# homeboard22.net
KiCad netlist of a schematic drawn in EAGLE
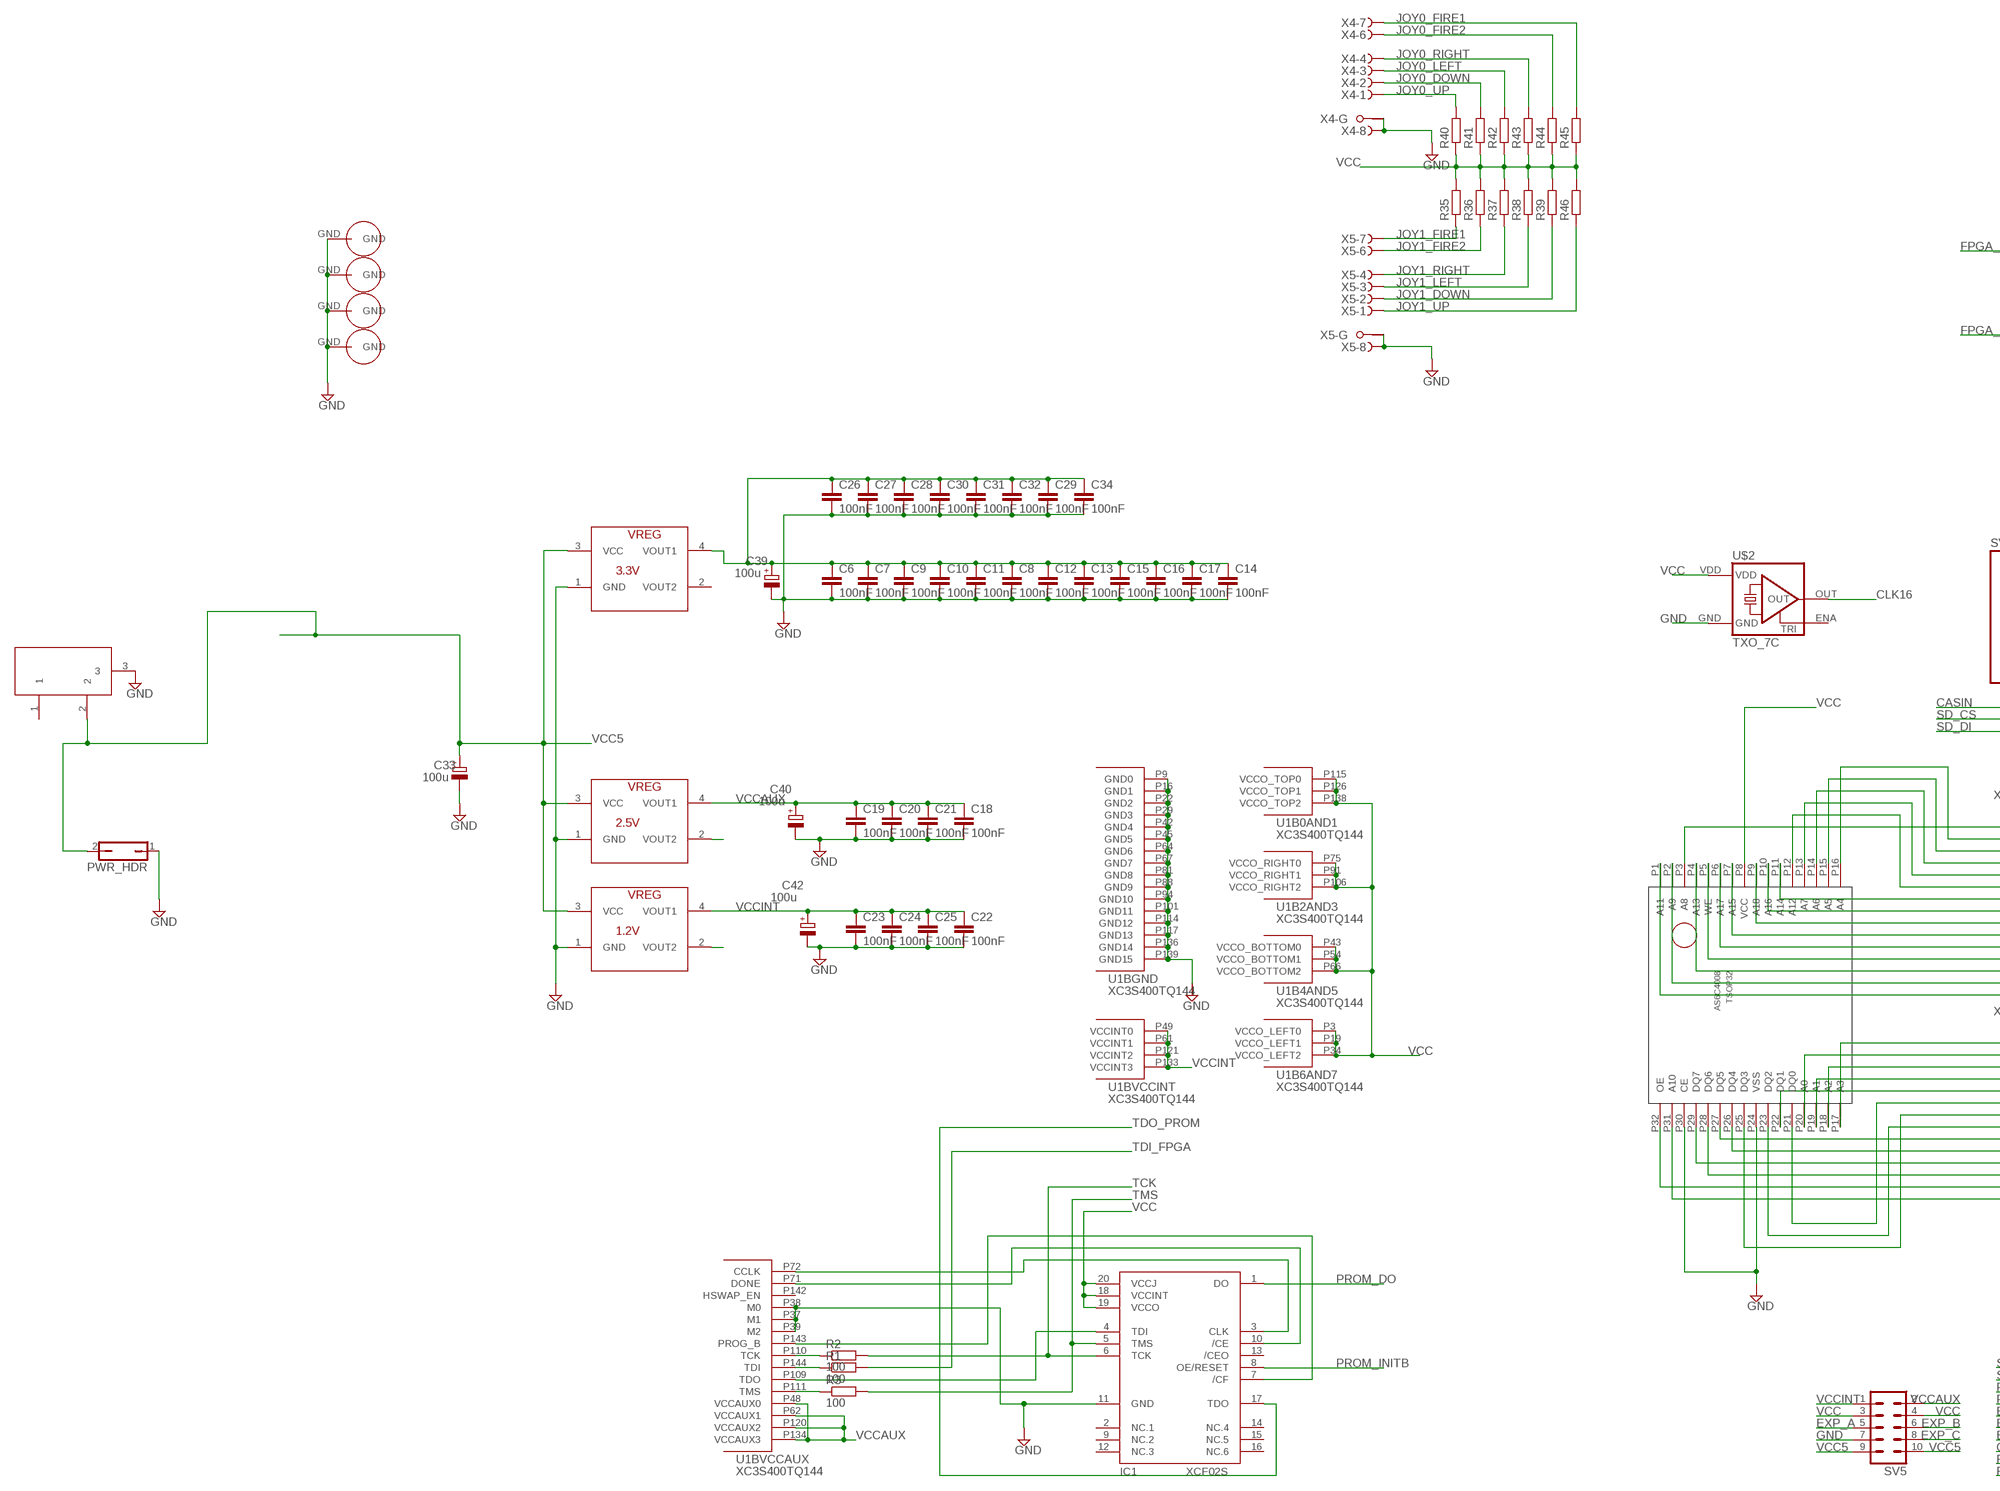
[diagram p0: schematic, sheet 1, part 1 of 3]
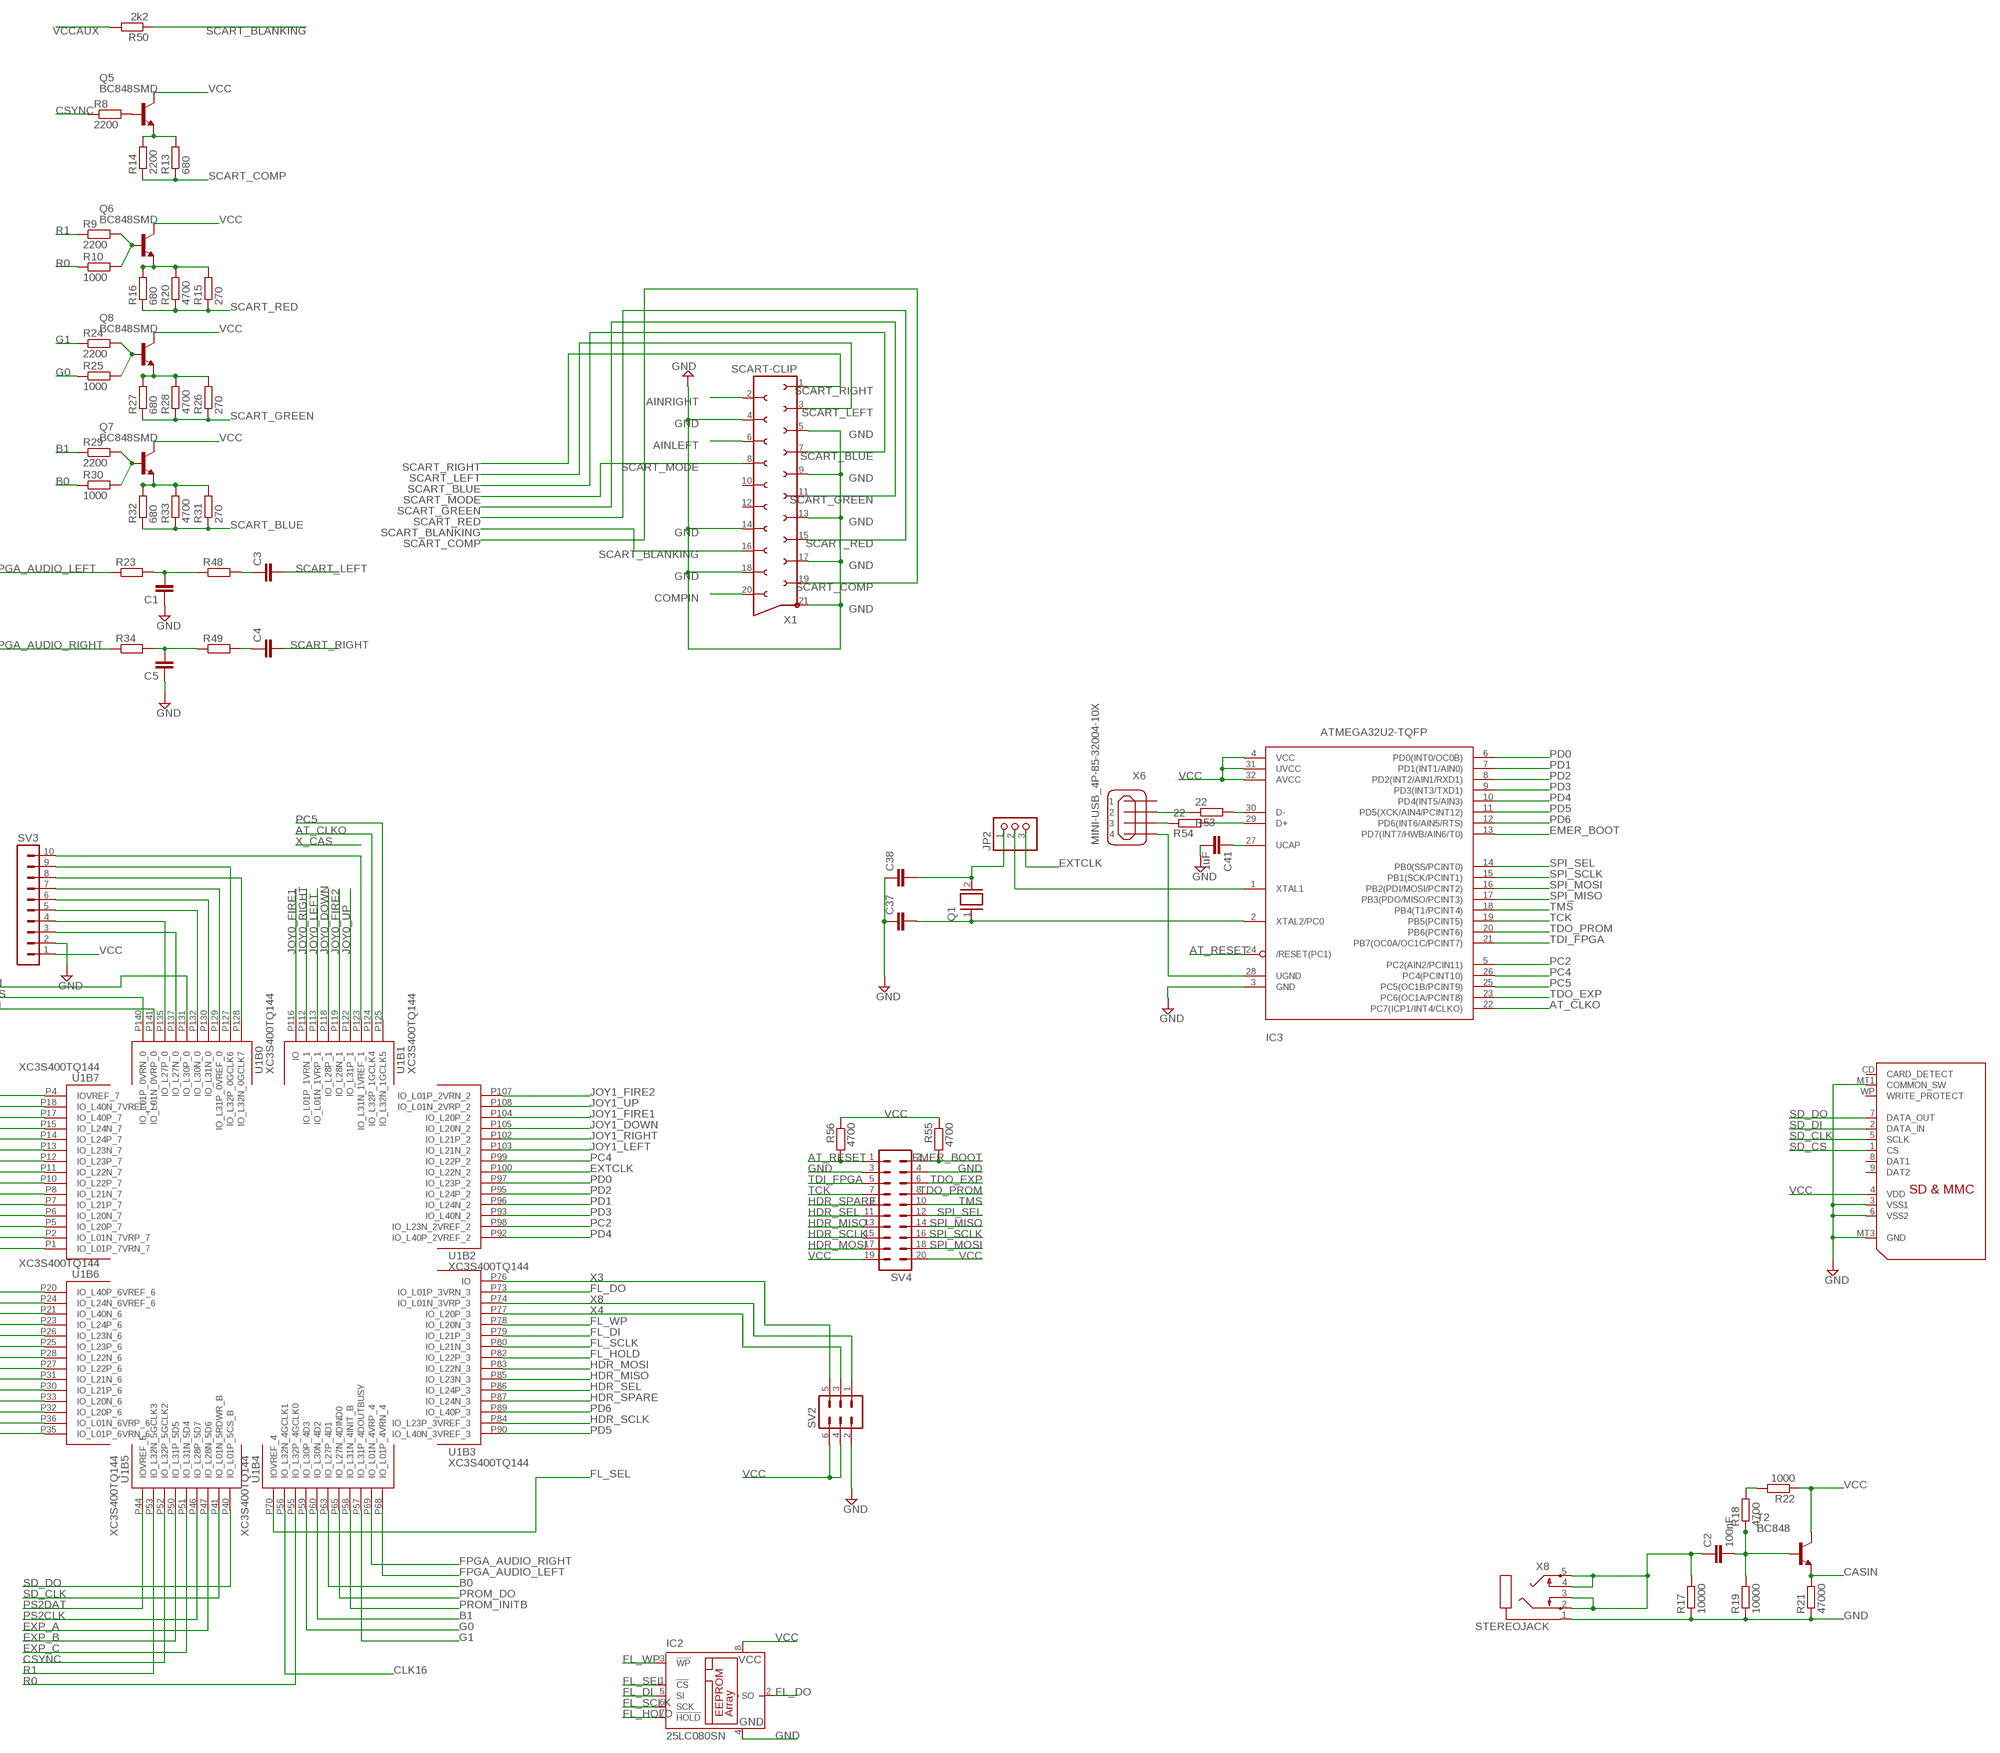
[diagram p1: schematic, sheet 1, part 2 of 3]
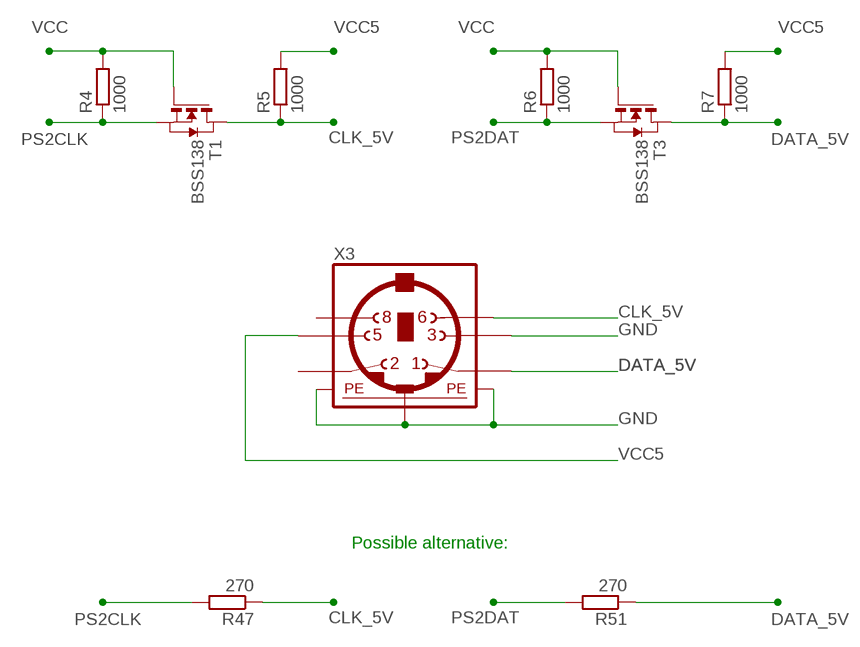
[diagram p2: schematic, sheet 1, part 3 of 3]

(export (version "E")
  (design (tool "Eeschema 10.0.6"))
  (components
    (comp (ref "C1")
      (value "C-EUC0603")
      (footprint "eagle-import:C0603")
      (libsource (lib "eagle-import") (part "resistor_C-EUC0603"))
    )
    (comp (ref "C2")
      (value "100nF")
      (footprint "eagle-import:C0603")
      (libsource (lib "eagle-import") (part "resistor_C-EUC0603"))
    )
    (comp (ref "C3")
      (value "C-EUC0603")
      (footprint "eagle-import:C0603")
      (libsource (lib "eagle-import") (part "resistor_C-EUC0603"))
    )
    (comp (ref "C4")
      (value "C-EUC0603")
      (footprint "eagle-import:C0603")
      (libsource (lib "eagle-import") (part "resistor_C-EUC0603"))
    )
    (comp (ref "C5")
      (value "C-EUC0603")
      (footprint "eagle-import:C0603")
      (libsource (lib "eagle-import") (part "resistor_C-EUC0603"))
    )
    (comp (ref "C6")
      (value "100nF")
      (footprint "eagle-import:C0603")
      (libsource (lib "eagle-import") (part "C-EUC0603"))
    )
    (comp (ref "C7")
      (value "100nF")
      (footprint "eagle-import:C0603")
      (libsource (lib "eagle-import") (part "C-EUC0603"))
    )
    (comp (ref "C8")
      (value "100nF")
      (footprint "eagle-import:C0603")
      (libsource (lib "eagle-import") (part "C-EUC0603"))
    )
    (comp (ref "C9")
      (value "100nF")
      (footprint "eagle-import:C0603")
      (libsource (lib "eagle-import") (part "C-EUC0603"))
    )
    (comp (ref "C10")
      (value "100nF")
      (footprint "eagle-import:C0603")
      (libsource (lib "eagle-import") (part "C-EUC0603"))
    )
    (comp (ref "C11")
      (value "100nF")
      (footprint "eagle-import:C0603")
      (libsource (lib "eagle-import") (part "C-EUC0603"))
    )
    (comp (ref "C12")
      (value "100nF")
      (footprint "eagle-import:C0603")
      (libsource (lib "eagle-import") (part "C-EUC0603"))
    )
    (comp (ref "C13")
      (value "100nF")
      (footprint "eagle-import:C0603")
      (libsource (lib "eagle-import") (part "C-EUC0603"))
    )
    (comp (ref "C14")
      (value "100nF")
      (footprint "eagle-import:C0603")
      (libsource (lib "eagle-import") (part "C-EUC0603"))
    )
    (comp (ref "C15")
      (value "100nF")
      (footprint "eagle-import:C0603")
      (libsource (lib "eagle-import") (part "C-EUC0603"))
    )
    (comp (ref "C16")
      (value "100nF")
      (footprint "eagle-import:C0603")
      (libsource (lib "eagle-import") (part "C-EUC0603"))
    )
    (comp (ref "C17")
      (value "100nF")
      (footprint "eagle-import:C0603")
      (libsource (lib "eagle-import") (part "C-EUC0603"))
    )
    (comp (ref "C18")
      (value "100nF")
      (footprint "eagle-import:C0603")
      (libsource (lib "eagle-import") (part "C-EUC0603"))
    )
    (comp (ref "C19")
      (value "100nF")
      (footprint "eagle-import:C0603")
      (libsource (lib "eagle-import") (part "C-EUC0603"))
    )
    (comp (ref "C20")
      (value "100nF")
      (footprint "eagle-import:C0603")
      (libsource (lib "eagle-import") (part "C-EUC0603"))
    )
    (comp (ref "C21")
      (value "100nF")
      (footprint "eagle-import:C0603")
      (libsource (lib "eagle-import") (part "C-EUC0603"))
    )
    (comp (ref "C22")
      (value "100nF")
      (footprint "eagle-import:C0603")
      (libsource (lib "eagle-import") (part "C-EUC0603"))
    )
    (comp (ref "C23")
      (value "100nF")
      (footprint "eagle-import:C0603")
      (libsource (lib "eagle-import") (part "C-EUC0603"))
    )
    (comp (ref "C24")
      (value "100nF")
      (footprint "eagle-import:C0603")
      (libsource (lib "eagle-import") (part "C-EUC0603"))
    )
    (comp (ref "C25")
      (value "100nF")
      (footprint "eagle-import:C0603")
      (libsource (lib "eagle-import") (part "C-EUC0603"))
    )
    (comp (ref "C26")
      (value "100nF")
      (footprint "eagle-import:C0603")
      (libsource (lib "eagle-import") (part "C-EUC0603"))
    )
    (comp (ref "C27")
      (value "100nF")
      (footprint "eagle-import:C0603")
      (libsource (lib "eagle-import") (part "C-EUC0603"))
    )
    (comp (ref "C28")
      (value "100nF")
      (footprint "eagle-import:C0603")
      (libsource (lib "eagle-import") (part "C-EUC0603"))
    )
    (comp (ref "C29")
      (value "100nF")
      (footprint "eagle-import:C0603")
      (libsource (lib "eagle-import") (part "C-EUC0603"))
    )
    (comp (ref "C30")
      (value "100nF")
      (footprint "eagle-import:C0603")
      (libsource (lib "eagle-import") (part "C-EUC0603"))
    )
    (comp (ref "C31")
      (value "100nF")
      (footprint "eagle-import:C0603")
      (libsource (lib "eagle-import") (part "C-EUC0603"))
    )
    (comp (ref "C32")
      (value "100nF")
      (footprint "eagle-import:C0603")
      (libsource (lib "eagle-import") (part "C-EUC0603"))
    )
    (comp (ref "C33")
      (value "100u")
      (footprint "eagle-import:PANASONIC_D")
      (libsource (lib "eagle-import") (part "CPOL-EUD"))
    )
    (comp (ref "C34")
      (value "100nF")
      (footprint "eagle-import:C0603")
      (libsource (lib "eagle-import") (part "C-EUC0603"))
    )
    (comp (ref "C37")
      (value "C-EUC0805")
      (footprint "eagle-import:C0805")
      (libsource (lib "eagle-import") (part "C-EUC0805"))
    )
    (comp (ref "C38")
      (value "C-EUC0805")
      (footprint "eagle-import:C0805")
      (libsource (lib "eagle-import") (part "C-EUC0805"))
    )
    (comp (ref "C39")
      (value "100u")
      (footprint "eagle-import:PANASONIC_D")
      (libsource (lib "eagle-import") (part "CPOL-EUD"))
    )
    (comp (ref "C40")
      (value "100u")
      (footprint "eagle-import:PANASONIC_D")
      (libsource (lib "eagle-import") (part "CPOL-EUD"))
    )
    (comp (ref "C41")
      (value "1uF")
      (footprint "eagle-import:C0805")
      (libsource (lib "eagle-import") (part "C-EUC0805"))
    )
    (comp (ref "C42")
      (value "100u")
      (footprint "eagle-import:PANASONIC_D")
      (libsource (lib "eagle-import") (part "CPOL-EUD"))
    )
    (comp (ref "IC1")
      (value "XCF02S")
      (footprint "eagle-import:VO20")
      (libsource (lib "eagle-import") (part "XCF02S"))
    )
    (comp (ref "IC2")
      (value "25LC080SN")
      (footprint "eagle-import:SO-08")
      (fields (field (name "MF") "MICROCHIP") (field (name "MPN") "25LC080/SN"))
      (libsource (lib "eagle-import") (part "25SNLC080"))
    )
    (comp (ref "IC3")
      (value "ATMEGA32U2-TQFP")
      (footprint "eagle-import:TQFP32-08")
      (libsource (lib "eagle-import") (part "ATMEGA32U2-TQFP"))
    )
    (comp (ref "JP2")
      (value "PINHD-1X3")
      (footprint "eagle-import:1X03")
      (libsource (lib "eagle-import") (part "PINHD-1X3"))
    )
    (comp (ref "PWR_HDR")
      (value "JP1Q")
      (footprint "eagle-import:JP1")
      (libsource (lib "eagle-import") (part "JP1Q"))
    )
    (comp (ref "Q1")
      (value "XTAL/S")
      (footprint "eagle-import:QS")
      (libsource (lib "eagle-import") (part "XTAL/S"))
    )
    (comp (ref "Q5")
      (value "BC848SMD")
      (footprint "eagle-import:SOT23")
      (libsource (lib "eagle-import") (part "BC848SMD"))
    )
    (comp (ref "Q6")
      (value "BC848SMD")
      (footprint "eagle-import:SOT23")
      (libsource (lib "eagle-import") (part "BC848SMD"))
    )
    (comp (ref "Q7")
      (value "BC848SMD")
      (footprint "eagle-import:SOT23")
      (libsource (lib "eagle-import") (part "BC848SMD"))
    )
    (comp (ref "Q8")
      (value "BC848SMD")
      (footprint "eagle-import:SOT23")
      (libsource (lib "eagle-import") (part "BC848SMD"))
    )
    (comp (ref "R1")
      (value "100")
      (footprint "eagle-import:R0805")
      (libsource (lib "eagle-import") (part "R-EU_R0805"))
    )
    (comp (ref "R2")
      (value "100")
      (footprint "eagle-import:R0805")
      (libsource (lib "eagle-import") (part "R-EU_R0805"))
    )
    (comp (ref "R3")
      (value "100")
      (footprint "eagle-import:R0805")
      (libsource (lib "eagle-import") (part "R-EU_R0805"))
    )
    (comp (ref "R4")
      (value "1000")
      (footprint "eagle-import:R0805")
      (libsource (lib "eagle-import") (part "R-EU_R0805"))
    )
    (comp (ref "R5")
      (value "1000")
      (footprint "eagle-import:R0805")
      (libsource (lib "eagle-import") (part "R-EU_R0805"))
    )
    (comp (ref "R6")
      (value "1000")
      (footprint "eagle-import:R0805")
      (libsource (lib "eagle-import") (part "R-EU_R0805"))
    )
    (comp (ref "R7")
      (value "1000")
      (footprint "eagle-import:R0805")
      (libsource (lib "eagle-import") (part "R-EU_R0805"))
    )
    (comp (ref "R8")
      (value "2200")
      (footprint "eagle-import:R0805")
      (libsource (lib "eagle-import") (part "R-EU_R0805"))
    )
    (comp (ref "R9")
      (value "2200")
      (footprint "eagle-import:R0805")
      (libsource (lib "eagle-import") (part "R-EU_R0805"))
    )
    (comp (ref "R10")
      (value "1000")
      (footprint "eagle-import:R0805")
      (libsource (lib "eagle-import") (part "R-EU_R0805"))
    )
    (comp (ref "R13")
      (value "680")
      (footprint "eagle-import:R0805")
      (libsource (lib "eagle-import") (part "R-EU_R0805"))
    )
    (comp (ref "R14")
      (value "2200")
      (footprint "eagle-import:R0805")
      (libsource (lib "eagle-import") (part "R-EU_R0805"))
    )
    (comp (ref "R15")
      (value "270")
      (footprint "eagle-import:R0805")
      (libsource (lib "eagle-import") (part "R-EU_R0805"))
    )
    (comp (ref "R16")
      (value "680")
      (footprint "eagle-import:R0805")
      (libsource (lib "eagle-import") (part "R-EU_R0805"))
    )
    (comp (ref "R17")
      (value "10000")
      (footprint "eagle-import:R0805")
      (libsource (lib "eagle-import") (part "R-EU_R0805"))
    )
    (comp (ref "R18")
      (value "4700")
      (footprint "eagle-import:R0805")
      (libsource (lib "eagle-import") (part "R-EU_R0805"))
    )
    (comp (ref "R19")
      (value "10000")
      (footprint "eagle-import:R0805")
      (libsource (lib "eagle-import") (part "R-EU_R0805"))
    )
    (comp (ref "R20")
      (value "4700")
      (footprint "eagle-import:R0805")
      (libsource (lib "eagle-import") (part "R-EU_R0805"))
    )
    (comp (ref "R21")
      (value "47000")
      (footprint "eagle-import:R0805")
      (libsource (lib "eagle-import") (part "R-EU_R0805"))
    )
    (comp (ref "R22")
      (value "1000")
      (footprint "eagle-import:R0805")
      (libsource (lib "eagle-import") (part "R-EU_R0805"))
    )
    (comp (ref "R23")
      (value "R-EU_M0805")
      (footprint "eagle-import:M0805")
      (libsource (lib "eagle-import") (part "resistor_R-EU_M0805"))
    )
    (comp (ref "R24")
      (value "2200")
      (footprint "eagle-import:R0805")
      (libsource (lib "eagle-import") (part "R-EU_R0805"))
    )
    (comp (ref "R25")
      (value "1000")
      (footprint "eagle-import:R0805")
      (libsource (lib "eagle-import") (part "R-EU_R0805"))
    )
    (comp (ref "R26")
      (value "270")
      (footprint "eagle-import:R0805")
      (libsource (lib "eagle-import") (part "R-EU_R0805"))
    )
    (comp (ref "R27")
      (value "680")
      (footprint "eagle-import:R0805")
      (libsource (lib "eagle-import") (part "R-EU_R0805"))
    )
    (comp (ref "R28")
      (value "4700")
      (footprint "eagle-import:R0805")
      (libsource (lib "eagle-import") (part "R-EU_R0805"))
    )
    (comp (ref "R29")
      (value "2200")
      (footprint "eagle-import:R0805")
      (libsource (lib "eagle-import") (part "R-EU_R0805"))
    )
    (comp (ref "R30")
      (value "1000")
      (footprint "eagle-import:R0805")
      (libsource (lib "eagle-import") (part "R-EU_R0805"))
    )
    (comp (ref "R31")
      (value "270")
      (footprint "eagle-import:R0805")
      (libsource (lib "eagle-import") (part "R-EU_R0805"))
    )
    (comp (ref "R32")
      (value "680")
      (footprint "eagle-import:R0805")
      (libsource (lib "eagle-import") (part "R-EU_R0805"))
    )
    (comp (ref "R33")
      (value "4700")
      (footprint "eagle-import:R0805")
      (libsource (lib "eagle-import") (part "R-EU_R0805"))
    )
    (comp (ref "R34")
      (value "R-EU_M0805")
      (footprint "eagle-import:M0805")
      (libsource (lib "eagle-import") (part "resistor_R-EU_M0805"))
    )
    (comp (ref "R35")
      (value "R-EU_M0805")
      (footprint "eagle-import:M0805")
      (libsource (lib "eagle-import") (part "resistor_R-EU_M0805"))
    )
    (comp (ref "R36")
      (value "R-EU_M0805")
      (footprint "eagle-import:M0805")
      (libsource (lib "eagle-import") (part "resistor_R-EU_M0805"))
    )
    (comp (ref "R37")
      (value "R-EU_M0805")
      (footprint "eagle-import:M0805")
      (libsource (lib "eagle-import") (part "resistor_R-EU_M0805"))
    )
    (comp (ref "R38")
      (value "R-EU_M0805")
      (footprint "eagle-import:M0805")
      (libsource (lib "eagle-import") (part "resistor_R-EU_M0805"))
    )
    (comp (ref "R39")
      (value "R-EU_M0805")
      (footprint "eagle-import:M0805")
      (libsource (lib "eagle-import") (part "resistor_R-EU_M0805"))
    )
    (comp (ref "R40")
      (value "R-EU_M0805")
      (footprint "eagle-import:M0805")
      (libsource (lib "eagle-import") (part "resistor_R-EU_M0805"))
    )
    (comp (ref "R41")
      (value "R-EU_M0805")
      (footprint "eagle-import:M0805")
      (libsource (lib "eagle-import") (part "resistor_R-EU_M0805"))
    )
    (comp (ref "R42")
      (value "R-EU_M0805")
      (footprint "eagle-import:M0805")
      (libsource (lib "eagle-import") (part "resistor_R-EU_M0805"))
    )
    (comp (ref "R43")
      (value "R-EU_M0805")
      (footprint "eagle-import:M0805")
      (libsource (lib "eagle-import") (part "resistor_R-EU_M0805"))
    )
    (comp (ref "R44")
      (value "R-EU_M0805")
      (footprint "eagle-import:M0805")
      (libsource (lib "eagle-import") (part "resistor_R-EU_M0805"))
    )
    (comp (ref "R45")
      (value "R-EU_M0805")
      (footprint "eagle-import:M0805")
      (libsource (lib "eagle-import") (part "resistor_R-EU_M0805"))
    )
    (comp (ref "R46")
      (value "R-EU_M0805")
      (footprint "eagle-import:M0805")
      (libsource (lib "eagle-import") (part "resistor_R-EU_M0805"))
    )
    (comp (ref "R47")
      (value "270")
      (footprint "eagle-import:R0805")
      (libsource (lib "eagle-import") (part "R-EU_R0805"))
    )
    (comp (ref "R48")
      (value "R-EU_M0805")
      (footprint "eagle-import:M0805")
      (libsource (lib "eagle-import") (part "resistor_R-EU_M0805"))
    )
    (comp (ref "R49")
      (value "R-EU_M0805")
      (footprint "eagle-import:M0805")
      (libsource (lib "eagle-import") (part "resistor_R-EU_M0805"))
    )
    (comp (ref "R50")
      (value "2k2")
      (footprint "eagle-import:M0805")
      (libsource (lib "eagle-import") (part "resistor_R-EU_M0805"))
    )
    (comp (ref "R51")
      (value "270")
      (footprint "eagle-import:R0805")
      (libsource (lib "eagle-import") (part "R-EU_R0805"))
    )
    (comp (ref "R53")
      (value "22")
      (footprint "eagle-import:R0805")
      (libsource (lib "eagle-import") (part "R-EU_R0805"))
    )
    (comp (ref "R54")
      (value "22")
      (footprint "eagle-import:R0805")
      (libsource (lib "eagle-import") (part "R-EU_R0805"))
    )
    (comp (ref "R55")
      (value "4700")
      (footprint "eagle-import:R0805")
      (libsource (lib "eagle-import") (part "R-EU_R0805"))
    )
    (comp (ref "R56")
      (value "4700")
      (footprint "eagle-import:R0805")
      (libsource (lib "eagle-import") (part "R-EU_R0805"))
    )
    (comp (ref "REG1.2")
      (value "1.2V")
      (footprint "eagle-import:SOT223")
      (libsource (lib "eagle-import") (part "NX1117"))
    )
    (comp (ref "REG2.5")
      (value "2.5V")
      (footprint "eagle-import:SOT223")
      (libsource (lib "eagle-import") (part "NX1117"))
    )
    (comp (ref "SV2")
      (value "MA03-2")
      (footprint "eagle-import:MA03-2")
      (libsource (lib "eagle-import") (part "MA03-2"))
    )
    (comp (ref "SV3")
      (value "MA10-1")
      (footprint "eagle-import:MA10-1")
      (libsource (lib "eagle-import") (part "MA10-1"))
    )
    (comp (ref "SV4")
      (value "MA10-2")
      (footprint "eagle-import:MA10-2")
      (libsource (lib "eagle-import") (part "MA10-2"))
    )
    (comp (ref "SV5")
      (value "MA05-2")
      (footprint "eagle-import:MA05-2")
      (libsource (lib "eagle-import") (part "MA05-2"))
    )
    (comp (ref "T1")
      (value "BSS138")
      (footprint "eagle-import:SOT-23")
      (libsource (lib "eagle-import") (part "NMOSSOT23"))
    )
    (comp (ref "T2")
      (value "BC848")
      (footprint "eagle-import:SOT23")
      (libsource (lib "eagle-import") (part "BC848"))
    )
    (comp (ref "T3")
      (value "BSS138")
      (footprint "eagle-import:SOT-23")
      (libsource (lib "eagle-import") (part "NMOSSOT23"))
    )
    (comp (ref "U$1")
      (value "GNDHOLE")
      (footprint "eagle-import:GNDHOLE")
      (libsource (lib "eagle-import") (part "GNDHOLE"))
    )
    (comp (ref "U$2")
      (value "TXO_7C")
      (footprint "eagle-import:OSC_7C")
      (libsource (lib "eagle-import") (part "TXO_7C"))
    )
    (comp (ref "U$3")
      (value "SDMMCNOHOLE")
      (footprint "eagle-import:SDCARD-NOHOLE")
      (libsource (lib "eagle-import") (part "SDMMCNOHOLE"))
    )
    (comp (ref "U$4")
      (value "3.3V")
      (footprint "eagle-import:SOT223")
      (libsource (lib "eagle-import") (part "NX1117"))
    )
    (comp (ref "U$6")
      (value "AS6C4008")
      (footprint "eagle-import:TSOP32")
      (libsource (lib "eagle-import") (part "AS6C4008"))
    )
    (comp (ref "U$7")
      (value "GNDHOLE")
      (footprint "eagle-import:GNDHOLE")
      (libsource (lib "eagle-import") (part "GNDHOLE"))
    )
    (comp (ref "U$8")
      (value "GNDHOLE")
      (footprint "eagle-import:GNDHOLE")
      (libsource (lib "eagle-import") (part "GNDHOLE"))
    )
    (comp (ref "U$9")
      (value "GNDHOLE")
      (footprint "eagle-import:GNDHOLE")
      (libsource (lib "eagle-import") (part "GNDHOLE"))
    )
    (comp (ref "U1")
      (value "XC3S400TQ144")
      (footprint "eagle-import:TQ144")
      (libsource (lib "eagle-import") (part "XC3S400TQ144"))
    )
    (comp (ref "X1")
      (value "SCART-CLIP")
      (footprint "eagle-import:SCART-CLIP")
      (libsource (lib "eagle-import") (part "SCART-CLIP"))
    )
    (comp (ref "X3")
      (value "MINI_DIN_6")
      (footprint "eagle-import:M_DIN6")
      (libsource (lib "eagle-import") (part "MINI_DIN_6"))
    )
    (comp (ref "X4")
      (value "F09HPS")
      (footprint "eagle-import:F09HP")
      (libsource (lib "eagle-import") (part "F09HPS"))
    )
    (comp (ref "X5")
      (value "F09HPS")
      (footprint "eagle-import:F09HP")
      (libsource (lib "eagle-import") (part "F09HPS"))
    )
    (comp (ref "X6")
      (value "MINI-USB_4P-85-32004-10X")
      (footprint "eagle-import:85-32004-10X")
      (libsource (lib "eagle-import") (part "MINI-USB_4P-85-32004-10X"))
    )
    (comp (ref "X7")
      (value "DC21MMX")
      (footprint "eagle-import:DC-21MM")
      (libsource (lib "eagle-import") (part "DC21MMX"))
    )
    (comp (ref "X8")
      (value "STEREOJACK")
      (footprint "eagle-import:20-0137")
      (libsource (lib "eagle-import") (part "STEREOJACK"))
    )
  )
  (nets
    (net (code "1") (name "/1") (class "Default")
      (node (ref "X7") (pin "1") (pinfunction "1_1") (pintype "power_in"))
    )
    (net (code "2") (name "/AINLEFT") (class "Default")
      (node (ref "X1") (pin "6") (pinfunction "6_6") (pintype "passive"))
    )
    (net (code "3") (name "/AINRIGHT") (class "Default")
      (node (ref "X1") (pin "2") (pinfunction "2_2") (pintype "passive"))
    )
    (net (code "4") (name "/AT_CLKO") (class "Default")
      (node (ref "IC3") (pin "22") (pinfunction "PC7(ICP1/INT4/CLKO)_22") (pintype "bidirectional"))
      (node (ref "U1") (pin "P124") (pinfunction "IO_L32P_1GCLK4_P124") (pintype "bidirectional"))
    )
    (net (code "5") (name "/AT_RESET") (class "Default")
      (node (ref "IC3") (pin "24") (pinfunction "/RESET(PC1)_24") (pintype "bidirectional"))
      (node (ref "R56") (pin "2") (pinfunction "2_2") (pintype "passive"))
      (node (ref "SV4") (pin "1") (pinfunction "1_1") (pintype "passive"))
    )
    (net (code "6") (name "/B0") (class "Default")
      (node (ref "R30") (pin "1") (pinfunction "1_1") (pintype "passive"))
      (node (ref "U1") (pin "P63") (pinfunction "IO_L27P_4D1_P63") (pintype "bidirectional"))
    )
    (net (code "7") (name "/B1") (class "Default")
      (node (ref "R29") (pin "1") (pinfunction "1_1") (pintype "passive"))
      (node (ref "U1") (pin "P60") (pinfunction "IO_L30N_4D2_P60") (pintype "bidirectional"))
    )
    (net (code "8") (name "/CASIN") (class "Default")
      (node (ref "R21") (pin "2") (pinfunction "2_2") (pintype "passive"))
      (node (ref "T2") (pin "2") (pinfunction "E_2") (pintype "passive"))
      (node (ref "U1") (pin "P131") (pinfunction "IO_L30P_0_P131") (pintype "bidirectional"))
    )
    (net (code "9") (name "/CLK16") (class "Default")
      (node (ref "U$2") (pin "OUT") (pinfunction "OUT_OUT") (pintype "output"))
      (node (ref "U1") (pin "P56") (pinfunction "IO_L32N_4GCLK1_P56") (pintype "bidirectional"))
    )
    (net (code "10") (name "/CLK_5V") (class "Default")
      (node (ref "R47") (pin "1") (pinfunction "1_1") (pintype "passive"))
      (node (ref "R5") (pin "1") (pinfunction "1_1") (pintype "passive"))
      (node (ref "T1") (pin "1") (pinfunction "D_1") (pintype "passive"))
      (node (ref "X3") (pin "6") (pinfunction "6_6") (pintype "passive"))
    )
    (net (code "11") (name "/COMPIN") (class "Default")
      (node (ref "X1") (pin "20") (pinfunction "20_20") (pintype "passive"))
    )
    (net (code "12") (name "/CSYNC") (class "Default")
      (node (ref "R8") (pin "1") (pinfunction "1_1") (pintype "passive"))
      (node (ref "U1") (pin "P52") (pinfunction "IO_L32P_5GCLK2_P52") (pintype "bidirectional"))
    )
    (net (code "13") (name "/DATA_5V") (class "Default")
      (node (ref "R51") (pin "1") (pinfunction "1_1") (pintype "passive"))
      (node (ref "R7") (pin "1") (pinfunction "1_1") (pintype "passive"))
      (node (ref "T3") (pin "1") (pinfunction "D_1") (pintype "passive"))
      (node (ref "X3") (pin "1") (pinfunction "1_1") (pintype "passive"))
    )
    (net (code "14") (name "/EMER_BOOT") (class "Default")
      (node (ref "IC3") (pin "13") (pinfunction "PD7(INT7/HWB/AIN6/T0)_13") (pintype "bidirectional"))
      (node (ref "R55") (pin "2") (pinfunction "2_2") (pintype "passive"))
      (node (ref "SV4") (pin "2") (pinfunction "2_2") (pintype "passive"))
    )
    (net (code "15") (name "/EXP_A") (class "Default")
      (node (ref "SV5") (pin "5") (pinfunction "5_5") (pintype "passive"))
      (node (ref "U1") (pin "P47") (pinfunction "IO_L28N_5D6_P47") (pintype "bidirectional"))
    )
    (net (code "16") (name "/EXP_B") (class "Default")
      (node (ref "SV5") (pin "6") (pinfunction "6_6") (pintype "passive"))
      (node (ref "U1") (pin "P50") (pinfunction "IO_L31P_5D5_P50") (pintype "bidirectional"))
    )
    (net (code "17") (name "/EXP_C") (class "Default")
      (node (ref "SV5") (pin "8") (pinfunction "8_8") (pintype "passive"))
      (node (ref "U1") (pin "P51") (pinfunction "IO_L31N_5D4_P51") (pintype "bidirectional"))
    )
    (net (code "18") (name "/EXTCLK") (class "Default")
      (node (ref "JP2") (pin "3") (pinfunction "3_3") (pintype "passive"))
      (node (ref "U1") (pin "P100") (pinfunction "IO_L22N_2_P100") (pintype "bidirectional"))
    )
    (net (code "19") (name "/FL_DI") (class "Default")
      (node (ref "IC2") (pin "5") (pinfunction "SI_5") (pintype "input"))
      (node (ref "U1") (pin "P79") (pinfunction "IO_L21P_3_P79") (pintype "bidirectional"))
    )
    (net (code "20") (name "/FL_DO") (class "Default")
      (node (ref "IC2") (pin "2") (pinfunction "SO_2") (pintype "bidirectional"))
      (node (ref "U1") (pin "P73") (pinfunction "IO_L01P_3VRN_3_P73") (pintype "bidirectional"))
    )
    (net (code "21") (name "/FL_HOLD") (class "Default")
      (node (ref "IC2") (pin "7") (pinfunction "~{HOLD}_7") (pintype "input"))
      (node (ref "U1") (pin "P82") (pinfunction "IO_L22P_3_P82") (pintype "bidirectional"))
    )
    (net (code "22") (name "/FL_SCLK") (class "Default")
      (node (ref "IC2") (pin "6") (pinfunction "SCK_6") (pintype "input"))
      (node (ref "U1") (pin "P80") (pinfunction "IO_L21N_3_P80") (pintype "bidirectional"))
    )
    (net (code "23") (name "/FL_SEL") (class "Default")
      (node (ref "IC2") (pin "1") (pinfunction "~{CS}_1") (pintype "input"))
      (node (ref "U1") (pin "P70") (pinfunction "IOVREF_4_P70") (pintype "bidirectional"))
    )
    (net (code "24") (name "/FL_WP") (class "Default")
      (node (ref "IC2") (pin "3") (pinfunction "~{WP}_3") (pintype "input"))
      (node (ref "U1") (pin "P78") (pinfunction "IO_L20N_3_P78") (pintype "bidirectional"))
    )
    (net (code "25") (name "/FPGA_AUDIO_LEFT") (class "Default")
      (node (ref "R23") (pin "1") (pinfunction "1_1") (pintype "passive"))
      (node (ref "U1") (pin "P68") (pinfunction "IO_L01P_4VRN_4_P68") (pintype "bidirectional"))
    )
    (net (code "26") (name "/FPGA_AUDIO_RIGHT") (class "Default")
      (node (ref "R34") (pin "1") (pinfunction "1_1") (pintype "passive"))
      (node (ref "U1") (pin "P69") (pinfunction "IO_L01N_4VRP_4_P69") (pintype "bidirectional"))
    )
    (net (code "27") (name "/G0") (class "Default")
      (node (ref "R25") (pin "1") (pinfunction "1_1") (pintype "passive"))
      (node (ref "U1") (pin "P59") (pinfunction "IO_L30P_4D3_P59") (pintype "bidirectional"))
    )
    (net (code "28") (name "/G1") (class "Default")
      (node (ref "R24") (pin "1") (pinfunction "1_1") (pintype "passive"))
      (node (ref "U1") (pin "P57") (pinfunction "IO_L31P_4DOUTBUSY_P57") (pintype "bidirectional"))
    )
    (net (code "29") (name "/HDR_MISO") (class "Default")
      (node (ref "SV4") (pin "13") (pinfunction "13_13") (pintype "passive"))
      (node (ref "U1") (pin "P85") (pinfunction "IO_L23N_3_P85") (pintype "bidirectional"))
    )
    (net (code "30") (name "/HDR_MOSI") (class "Default")
      (node (ref "SV4") (pin "17") (pinfunction "17_17") (pintype "passive"))
      (node (ref "U1") (pin "P83") (pinfunction "IO_L22N_3_P83") (pintype "bidirectional"))
    )
    (net (code "31") (name "/HDR_SCLK") (class "Default")
      (node (ref "SV4") (pin "15") (pinfunction "15_15") (pintype "passive"))
      (node (ref "U1") (pin "P84") (pinfunction "IO_L23P_3VREF_3_P84") (pintype "bidirectional"))
    )
    (net (code "32") (name "/HDR_SEL") (class "Default")
      (node (ref "SV4") (pin "11") (pinfunction "11_11") (pintype "passive"))
      (node (ref "U1") (pin "P86") (pinfunction "IO_L24P_3_P86") (pintype "bidirectional"))
    )
    (net (code "33") (name "/HDR_SPARE") (class "Default")
      (node (ref "SV4") (pin "9") (pinfunction "9_9") (pintype "passive"))
      (node (ref "U1") (pin "P87") (pinfunction "IO_L24N_3_P87") (pintype "bidirectional"))
    )
    (net (code "34") (name "/JOY0_DOWN") (class "Default")
      (node (ref "R41") (pin "2") (pinfunction "2_2") (pintype "passive"))
      (node (ref "U1") (pin "P118") (pinfunction "IO_L28P_1_P118") (pintype "bidirectional"))
      (node (ref "X4") (pin "2") (pinfunction "F_2") (pintype "passive"))
    )
    (net (code "35") (name "/JOY0_FIRE1") (class "Default")
      (node (ref "R45") (pin "2") (pinfunction "2_2") (pintype "passive"))
      (node (ref "U1") (pin "P116") (pinfunction "IO_P116") (pintype "bidirectional"))
      (node (ref "X4") (pin "7") (pinfunction "F_7") (pintype "passive"))
    )
    (net (code "36") (name "/JOY0_FIRE2") (class "Default")
      (node (ref "R44") (pin "2") (pinfunction "2_2") (pintype "passive"))
      (node (ref "U1") (pin "P119") (pinfunction "IO_L28N_1_P119") (pintype "bidirectional"))
      (node (ref "X4") (pin "6") (pinfunction "F_6") (pintype "passive"))
    )
    (net (code "37") (name "/JOY0_LEFT") (class "Default")
      (node (ref "R42") (pin "2") (pinfunction "2_2") (pintype "passive"))
      (node (ref "U1") (pin "P113") (pinfunction "IO_L01N_1VRP_1_P113") (pintype "bidirectional"))
      (node (ref "X4") (pin "3") (pinfunction "F_3") (pintype "passive"))
    )
    (net (code "38") (name "/JOY0_RIGHT") (class "Default")
      (node (ref "R43") (pin "2") (pinfunction "2_2") (pintype "passive"))
      (node (ref "U1") (pin "P112") (pinfunction "IO_L01P_1VRN_1_P112") (pintype "bidirectional"))
      (node (ref "X4") (pin "4") (pinfunction "F_4") (pintype "passive"))
    )
    (net (code "39") (name "/JOY0_UP") (class "Default")
      (node (ref "R40") (pin "2") (pinfunction "2_2") (pintype "passive"))
      (node (ref "U1") (pin "P122") (pinfunction "IO_L31P_1_P122") (pintype "bidirectional"))
      (node (ref "X4") (pin "1") (pinfunction "F_1") (pintype "passive"))
    )
    (net (code "40") (name "/JOY1_DOWN") (class "Default")
      (node (ref "R39") (pin "1") (pinfunction "1_1") (pintype "passive"))
      (node (ref "U1") (pin "P105") (pinfunction "IO_L20N_2_P105") (pintype "bidirectional"))
      (node (ref "X5") (pin "2") (pinfunction "F_2") (pintype "passive"))
    )
    (net (code "41") (name "/JOY1_FIRE1") (class "Default")
      (node (ref "R35") (pin "1") (pinfunction "1_1") (pintype "passive"))
      (node (ref "U1") (pin "P104") (pinfunction "IO_L20P_2_P104") (pintype "bidirectional"))
      (node (ref "X5") (pin "7") (pinfunction "F_7") (pintype "passive"))
    )
    (net (code "42") (name "/JOY1_FIRE2") (class "Default")
      (node (ref "R36") (pin "1") (pinfunction "1_1") (pintype "passive"))
      (node (ref "U1") (pin "P107") (pinfunction "IO_L01P_2VRN_2_P107") (pintype "bidirectional"))
      (node (ref "X5") (pin "6") (pinfunction "F_6") (pintype "passive"))
    )
    (net (code "43") (name "/JOY1_LEFT") (class "Default")
      (node (ref "R38") (pin "1") (pinfunction "1_1") (pintype "passive"))
      (node (ref "U1") (pin "P103") (pinfunction "IO_L21N_2_P103") (pintype "bidirectional"))
      (node (ref "X5") (pin "3") (pinfunction "F_3") (pintype "passive"))
    )
    (net (code "44") (name "/JOY1_RIGHT") (class "Default")
      (node (ref "R37") (pin "1") (pinfunction "1_1") (pintype "passive"))
      (node (ref "U1") (pin "P102") (pinfunction "IO_L21P_2_P102") (pintype "bidirectional"))
      (node (ref "X5") (pin "4") (pinfunction "F_4") (pintype "passive"))
    )
    (net (code "45") (name "/JOY1_UP") (class "Default")
      (node (ref "R46") (pin "1") (pinfunction "1_1") (pintype "passive"))
      (node (ref "U1") (pin "P108") (pinfunction "IO_L01N_2VRP_2_P108") (pintype "bidirectional"))
      (node (ref "X5") (pin "1") (pinfunction "F_1") (pintype "passive"))
    )
    (net (code "46") (name "/PC2") (class "Default")
      (node (ref "IC3") (pin "5") (pinfunction "PC2(AIN2/PCIN11)_5") (pintype "bidirectional"))
      (node (ref "U1") (pin "P98") (pinfunction "IO_L23N_2VREF_2_P98") (pintype "bidirectional"))
    )
    (net (code "47") (name "/PC4") (class "Default")
      (node (ref "IC3") (pin "26") (pinfunction "PC4(PCINT10)_26") (pintype "bidirectional"))
      (node (ref "U1") (pin "P99") (pinfunction "IO_L22P_2_P99") (pintype "bidirectional"))
    )
    (net (code "48") (name "/PC5") (class "Default")
      (node (ref "IC3") (pin "25") (pinfunction "PC5(OC1B/PCINT9)_25") (pintype "bidirectional"))
      (node (ref "U1") (pin "P125") (pinfunction "IO_L32N_1GCLK5_P125") (pintype "bidirectional"))
    )
    (net (code "49") (name "/PD0") (class "Default")
      (node (ref "IC3") (pin "6") (pinfunction "PD0(INT0/OC0B)_6") (pintype "bidirectional"))
      (node (ref "U1") (pin "P97") (pinfunction "IO_L23P_2_P97") (pintype "bidirectional"))
    )
    (net (code "50") (name "/PD1") (class "Default")
      (node (ref "IC3") (pin "7") (pinfunction "PD1(INT1/AIN0)_7") (pintype "bidirectional"))
      (node (ref "U1") (pin "P96") (pinfunction "IO_L24N_2_P96") (pintype "bidirectional"))
    )
    (net (code "51") (name "/PD2") (class "Default")
      (node (ref "IC3") (pin "8") (pinfunction "PD2(INT2/AIN1/RXD1)_8") (pintype "bidirectional"))
      (node (ref "U1") (pin "P95") (pinfunction "IO_L24P_2_P95") (pintype "bidirectional"))
    )
    (net (code "52") (name "/PD3") (class "Default")
      (node (ref "IC3") (pin "9") (pinfunction "PD3(INT3/TXD1)_9") (pintype "bidirectional"))
      (node (ref "U1") (pin "P93") (pinfunction "IO_L40N_2_P93") (pintype "bidirectional"))
    )
    (net (code "53") (name "/PD4") (class "Default")
      (node (ref "IC3") (pin "10") (pinfunction "PD4(INT5/AIN3)_10") (pintype "bidirectional"))
      (node (ref "U1") (pin "P92") (pinfunction "IO_L40P_2VREF_2_P92") (pintype "bidirectional"))
    )
    (net (code "54") (name "/PD5") (class "Default")
      (node (ref "IC3") (pin "11") (pinfunction "PD5(XCK/AIN4/PCINT12)_11") (pintype "bidirectional"))
      (node (ref "U1") (pin "P90") (pinfunction "IO_L40N_3VREF_3_P90") (pintype "bidirectional"))
    )
    (net (code "55") (name "/PD6") (class "Default")
      (node (ref "IC3") (pin "12") (pinfunction "PD6(INT6/AIN5/RTS)_12") (pintype "bidirectional"))
      (node (ref "U1") (pin "P89") (pinfunction "IO_L40P_3_P89") (pintype "bidirectional"))
    )
    (net (code "56") (name "/PROM_DO") (class "Default")
      (node (ref "IC1") (pin "1") (pinfunction "DO_1") (pintype "bidirectional"))
      (node (ref "U1") (pin "P65") (pinfunction "IO_L27N_4DIND0_P65") (pintype "bidirectional"))
    )
    (net (code "57") (name "/PROM_INITB") (class "Default")
      (node (ref "IC1") (pin "8") (pinfunction "OE/RESET_8") (pintype "bidirectional"))
      (node (ref "U1") (pin "P58") (pinfunction "IO_L31N_4INIT_B_P58") (pintype "bidirectional"))
    )
    (net (code "58") (name "/PS2CLK") (class "Default")
      (node (ref "R4") (pin "1") (pinfunction "1_1") (pintype "passive"))
      (node (ref "R47") (pin "2") (pinfunction "2_2") (pintype "passive"))
      (node (ref "T1") (pin "2") (pinfunction "S_2") (pintype "passive"))
      (node (ref "U1") (pin "P46") (pinfunction "IO_L28P_5D7_P46") (pintype "bidirectional"))
    )
    (net (code "59") (name "/PS2DAT") (class "Default")
      (node (ref "R51") (pin "2") (pinfunction "2_2") (pintype "passive"))
      (node (ref "R6") (pin "1") (pinfunction "1_1") (pintype "passive"))
      (node (ref "T3") (pin "2") (pinfunction "S_2") (pintype "passive"))
      (node (ref "U1") (pin "P44") (pinfunction "IOVREF_5_P44") (pintype "bidirectional"))
    )
    (net (code "60") (name "/R0") (class "Default")
      (node (ref "R10") (pin "1") (pinfunction "1_1") (pintype "passive"))
      (node (ref "U1") (pin "P55") (pinfunction "IO_L32P_4GCLK0_P55") (pintype "bidirectional"))
    )
    (net (code "61") (name "/R1") (class "Default")
      (node (ref "R9") (pin "1") (pinfunction "1_1") (pintype "passive"))
      (node (ref "U1") (pin "P53") (pinfunction "IO_L32N_5GCLK3_P53") (pintype "bidirectional"))
    )
    (net (code "62") (name "/SCART_BLANKING") (class "Default")
      (node (ref "R50") (pin "1") (pinfunction "1_1") (pintype "passive"))
      (node (ref "X1") (pin "16") (pinfunction "16_16") (pintype "passive"))
    )
    (net (code "63") (name "/SCART_BLUE") (class "Default")
      (node (ref "R31") (pin "1") (pinfunction "1_1") (pintype "passive"))
      (node (ref "R32") (pin "1") (pinfunction "1_1") (pintype "passive"))
      (node (ref "R33") (pin "1") (pinfunction "1_1") (pintype "passive"))
      (node (ref "X1") (pin "7") (pinfunction "7_7") (pintype "passive"))
    )
    (net (code "64") (name "/SCART_COMP") (class "Default")
      (node (ref "R13") (pin "1") (pinfunction "1_1") (pintype "passive"))
      (node (ref "R14") (pin "1") (pinfunction "1_1") (pintype "passive"))
      (node (ref "X1") (pin "19") (pinfunction "19_19") (pintype "passive"))
    )
    (net (code "65") (name "/SCART_GREEN") (class "Default")
      (node (ref "R26") (pin "1") (pinfunction "1_1") (pintype "passive"))
      (node (ref "R27") (pin "1") (pinfunction "1_1") (pintype "passive"))
      (node (ref "R28") (pin "1") (pinfunction "1_1") (pintype "passive"))
      (node (ref "X1") (pin "11") (pinfunction "11_11") (pintype "passive"))
    )
    (net (code "66") (name "/SCART_LEFT") (class "Default")
      (node (ref "C3") (pin "2") (pinfunction "2_2") (pintype "passive"))
      (node (ref "X1") (pin "3") (pinfunction "3_3") (pintype "passive"))
    )
    (net (code "67") (name "/SCART_MODE") (class "Default")
      (node (ref "X1") (pin "8") (pinfunction "8_8") (pintype "passive"))
    )
    (net (code "68") (name "/SCART_RED") (class "Default")
      (node (ref "R15") (pin "1") (pinfunction "1_1") (pintype "passive"))
      (node (ref "R16") (pin "1") (pinfunction "1_1") (pintype "passive"))
      (node (ref "R20") (pin "1") (pinfunction "1_1") (pintype "passive"))
      (node (ref "X1") (pin "15") (pinfunction "15_15") (pintype "passive"))
    )
    (net (code "69") (name "/SCART_RIGHT") (class "Default")
      (node (ref "C4") (pin "2") (pinfunction "2_2") (pintype "passive"))
      (node (ref "X1") (pin "1") (pinfunction "1_1") (pintype "passive"))
    )
    (net (code "70") (name "/SD_CLK") (class "Default")
      (node (ref "U$3") (pin "5") (pinfunction "SCLK_5") (pintype "input"))
      (node (ref "U1") (pin "P41") (pinfunction "IO_L01N_5RDWR_B_P41") (pintype "bidirectional"))
    )
    (net (code "71") (name "/SD_CS") (class "Default")
      (node (ref "U$3") (pin "1") (pinfunction "CS_1") (pintype "input"))
      (node (ref "U1") (pin "P140") (pinfunction "IO_L01P_0VRN_0_P140") (pintype "bidirectional"))
    )
    (net (code "72") (name "/SD_DI") (class "Default")
      (node (ref "U$3") (pin "2") (pinfunction "DATA_IN_2") (pintype "input"))
      (node (ref "U1") (pin "P141") (pinfunction "IO_L01N_0VRP_0_P141") (pintype "bidirectional"))
    )
    (net (code "73") (name "/SD_DO") (class "Default")
      (node (ref "U$3") (pin "7") (pinfunction "DATA_OUT_7") (pintype "output"))
      (node (ref "U1") (pin "P40") (pinfunction "IO_L01P_5CS_B_P40") (pintype "bidirectional"))
    )
    (net (code "74") (name "/SPI_MISO") (class "Default")
      (node (ref "IC3") (pin "17") (pinfunction "PB3(PDO/MISO/PCINT3)_17") (pintype "bidirectional"))
      (node (ref "SV4") (pin "14") (pinfunction "14_14") (pintype "passive"))
    )
    (net (code "75") (name "/SPI_MOSI") (class "Default")
      (node (ref "IC3") (pin "16") (pinfunction "PB2(PDI/MOSI/PCINT2)_16") (pintype "bidirectional"))
      (node (ref "SV4") (pin "18") (pinfunction "18_18") (pintype "passive"))
    )
    (net (code "76") (name "/SPI_SCLK") (class "Default")
      (node (ref "IC3") (pin "15") (pinfunction "PB1(SCK/PCINT1)_15") (pintype "bidirectional"))
      (node (ref "SV4") (pin "16") (pinfunction "16_16") (pintype "passive"))
    )
    (net (code "77") (name "/SPI_SEL") (class "Default")
      (node (ref "IC3") (pin "14") (pinfunction "PB0(SS/PCINT0)_14") (pintype "bidirectional"))
      (node (ref "SV4") (pin "12") (pinfunction "12_12") (pintype "passive"))
    )
    (net (code "78") (name "/TCK") (class "Default")
      (node (ref "IC1") (pin "6") (pinfunction "TCK_6") (pintype "bidirectional"))
      (node (ref "IC3") (pin "19") (pinfunction "PB5(PCINT5)_19") (pintype "bidirectional"))
      (node (ref "R2") (pin "2") (pinfunction "2_2") (pintype "passive"))
      (node (ref "SV4") (pin "7") (pinfunction "7_7") (pintype "passive"))
    )
    (net (code "79") (name "/TDI_FPGA") (class "Default")
      (node (ref "IC3") (pin "21") (pinfunction "PB7(OC0A/OC1C/PCINT7)_21") (pintype "bidirectional"))
      (node (ref "R1") (pin "2") (pinfunction "2_2") (pintype "passive"))
      (node (ref "SV4") (pin "5") (pinfunction "5_5") (pintype "passive"))
    )
    (net (code "80") (name "/TDO_EXP") (class "Default")
      (node (ref "IC3") (pin "23") (pinfunction "PC6(OC1A/PCINT8)_23") (pintype "bidirectional"))
      (node (ref "SV4") (pin "6") (pinfunction "6_6") (pintype "passive"))
    )
    (net (code "81") (name "/TDO_PROM") (class "Default")
      (node (ref "IC1") (pin "17") (pinfunction "TDO_17") (pintype "bidirectional"))
      (node (ref "IC3") (pin "20") (pinfunction "PB6(PCINT6)_20") (pintype "bidirectional"))
      (node (ref "SV4") (pin "8") (pinfunction "8_8") (pintype "passive"))
    )
    (net (code "82") (name "/TMS") (class "Default")
      (node (ref "IC1") (pin "5") (pinfunction "TMS_5") (pintype "bidirectional"))
      (node (ref "IC3") (pin "18") (pinfunction "PB4(T1/PCINT4)_18") (pintype "bidirectional"))
      (node (ref "R3") (pin "2") (pinfunction "2_2") (pintype "passive"))
      (node (ref "SV4") (pin "10") (pinfunction "10_10") (pintype "passive"))
    )
    (net (code "83") (name "/VCC") (class "Default")
      (node (ref "C10") (pin "1") (pinfunction "1_1") (pintype "passive"))
      (node (ref "C11") (pin "1") (pinfunction "1_1") (pintype "passive"))
      (node (ref "C12") (pin "1") (pinfunction "1_1") (pintype "passive"))
      (node (ref "C13") (pin "1") (pinfunction "1_1") (pintype "passive"))
      (node (ref "C14") (pin "1") (pinfunction "1_1") (pintype "passive"))
      (node (ref "C15") (pin "1") (pinfunction "1_1") (pintype "passive"))
      (node (ref "C16") (pin "1") (pinfunction "1_1") (pintype "passive"))
      (node (ref "C17") (pin "1") (pinfunction "1_1") (pintype "passive"))
      (node (ref "C26") (pin "1") (pinfunction "1_1") (pintype "passive"))
      (node (ref "C27") (pin "1") (pinfunction "1_1") (pintype "passive"))
      (node (ref "C28") (pin "1") (pinfunction "1_1") (pintype "passive"))
      (node (ref "C29") (pin "1") (pinfunction "1_1") (pintype "passive"))
      (node (ref "C30") (pin "1") (pinfunction "1_1") (pintype "passive"))
      (node (ref "C31") (pin "1") (pinfunction "1_1") (pintype "passive"))
      (node (ref "C32") (pin "1") (pinfunction "1_1") (pintype "passive"))
      (node (ref "C34") (pin "1") (pinfunction "1_1") (pintype "passive"))
      (node (ref "C39") (pin "+") (pinfunction "+_+") (pintype "passive"))
      (node (ref "C6") (pin "1") (pinfunction "1_1") (pintype "passive"))
      (node (ref "C7") (pin "1") (pinfunction "1_1") (pintype "passive"))
      (node (ref "C8") (pin "1") (pinfunction "1_1") (pintype "passive"))
      (node (ref "C9") (pin "1") (pinfunction "1_1") (pintype "passive"))
      (node (ref "IC1") (pin "18") (pinfunction "VCCINT_18") (pintype "bidirectional"))
      (node (ref "IC1") (pin "19") (pinfunction "VCCO_19") (pintype "bidirectional"))
      (node (ref "IC1") (pin "20") (pinfunction "VCCJ_20") (pintype "bidirectional"))
      (node (ref "IC2") (pin "8") (pinfunction "VCC_8") (pintype "power_in"))
      (node (ref "IC3") (pin "31") (pinfunction "UVCC_31") (pintype "bidirectional"))
      (node (ref "IC3") (pin "32") (pinfunction "AVCC_32") (pintype "bidirectional"))
      (node (ref "IC3") (pin "4") (pinfunction "VCC_4") (pintype "bidirectional"))
      (node (ref "Q5") (pin "3") (pinfunction "C_3") (pintype "passive"))
      (node (ref "Q6") (pin "3") (pinfunction "C_3") (pintype "passive"))
      (node (ref "Q7") (pin "3") (pinfunction "C_3") (pintype "passive"))
      (node (ref "Q8") (pin "3") (pinfunction "C_3") (pintype "passive"))
      (node (ref "R22") (pin "1") (pinfunction "1_1") (pintype "passive"))
      (node (ref "R35") (pin "2") (pinfunction "2_2") (pintype "passive"))
      (node (ref "R36") (pin "2") (pinfunction "2_2") (pintype "passive"))
      (node (ref "R37") (pin "2") (pinfunction "2_2") (pintype "passive"))
      (node (ref "R38") (pin "2") (pinfunction "2_2") (pintype "passive"))
      (node (ref "R39") (pin "2") (pinfunction "2_2") (pintype "passive"))
      (node (ref "R4") (pin "2") (pinfunction "2_2") (pintype "passive"))
      (node (ref "R40") (pin "1") (pinfunction "1_1") (pintype "passive"))
      (node (ref "R41") (pin "1") (pinfunction "1_1") (pintype "passive"))
      (node (ref "R42") (pin "1") (pinfunction "1_1") (pintype "passive"))
      (node (ref "R43") (pin "1") (pinfunction "1_1") (pintype "passive"))
      (node (ref "R44") (pin "1") (pinfunction "1_1") (pintype "passive"))
      (node (ref "R45") (pin "1") (pinfunction "1_1") (pintype "passive"))
      (node (ref "R46") (pin "2") (pinfunction "2_2") (pintype "passive"))
      (node (ref "R55") (pin "1") (pinfunction "1_1") (pintype "passive"))
      (node (ref "R56") (pin "1") (pinfunction "1_1") (pintype "passive"))
      (node (ref "R6") (pin "2") (pinfunction "2_2") (pintype "passive"))
      (node (ref "SV2") (pin "4") (pinfunction "4_4") (pintype "passive"))
      (node (ref "SV2") (pin "6") (pinfunction "6_6") (pintype "passive"))
      (node (ref "SV3") (pin "1") (pinfunction "1_1") (pintype "passive"))
      (node (ref "SV4") (pin "19") (pinfunction "19_19") (pintype "passive"))
      (node (ref "SV4") (pin "20") (pinfunction "20_20") (pintype "passive"))
      (node (ref "SV5") (pin "3") (pinfunction "3_3") (pintype "passive"))
      (node (ref "SV5") (pin "4") (pinfunction "4_4") (pintype "passive"))
      (node (ref "T1") (pin "3") (pinfunction "G_3") (pintype "passive"))
      (node (ref "T2") (pin "3") (pinfunction "C_3") (pintype "passive"))
      (node (ref "T3") (pin "3") (pinfunction "G_3") (pintype "passive"))
      (node (ref "U$2") (pin "VDD") (pinfunction "VDD_VDD") (pintype "power_in"))
      (node (ref "U$3") (pin "4") (pinfunction "VDD_4") (pintype "power_in"))
      (node (ref "U$4") (pin "4") (pinfunction "VOUT1_4") (pintype "bidirectional"))
      (node (ref "U$6") (pin "P8") (pinfunction "VCC_P8") (pintype "bidirectional"))
      (node (ref "U1") (pin "P106") (pinfunction "VCCO_RIGHT2_P106") (pintype "passive"))
      (node (ref "U1") (pin "P115") (pinfunction "VCCO_TOP0_P115") (pintype "passive"))
      (node (ref "U1") (pin "P126") (pinfunction "VCCO_TOP1_P126") (pintype "passive"))
      (node (ref "U1") (pin "P138") (pinfunction "VCCO_TOP2_P138") (pintype "passive"))
      (node (ref "U1") (pin "P19") (pinfunction "VCCO_LEFT1_P19") (pintype "passive"))
      (node (ref "U1") (pin "P3") (pinfunction "VCCO_LEFT0_P3") (pintype "passive"))
      (node (ref "U1") (pin "P34") (pinfunction "VCCO_LEFT2_P34") (pintype "passive"))
      (node (ref "U1") (pin "P43") (pinfunction "VCCO_BOTTOM0_P43") (pintype "passive"))
      (node (ref "U1") (pin "P54") (pinfunction "VCCO_BOTTOM1_P54") (pintype "passive"))
      (node (ref "U1") (pin "P66") (pinfunction "VCCO_BOTTOM2_P66") (pintype "passive"))
      (node (ref "U1") (pin "P75") (pinfunction "VCCO_RIGHT0_P75") (pintype "passive"))
      (node (ref "U1") (pin "P91") (pinfunction "VCCO_RIGHT1_P91") (pintype "passive"))
    )
    (net (code "84") (name "/VCC5") (class "Default")
      (node (ref "C33") (pin "+") (pinfunction "+_+") (pintype "passive"))
      (node (ref "PWR_HDR") (pin "2") (pinfunction "2_2") (pintype "passive"))
      (node (ref "R5") (pin "2") (pinfunction "2_2") (pintype "passive"))
      (node (ref "R7") (pin "2") (pinfunction "2_2") (pintype "passive"))
      (node (ref "REG1.2") (pin "3") (pinfunction "VCC_3") (pintype "bidirectional"))
      (node (ref "REG2.5") (pin "3") (pinfunction "VCC_3") (pintype "bidirectional"))
      (node (ref "SV5") (pin "10") (pinfunction "10_10") (pintype "passive"))
      (node (ref "SV5") (pin "9") (pinfunction "9_9") (pintype "passive"))
      (node (ref "U$4") (pin "3") (pinfunction "VCC_3") (pintype "bidirectional"))
      (node (ref "X3") (pin "5") (pinfunction "5_5") (pintype "passive"))
      (node (ref "X7") (pin "2") (pinfunction "2_2") (pintype "power_in"))
    )
    (net (code "85") (name "/VCCAUX") (class "Default")
      (node (ref "C18") (pin "1") (pinfunction "1_1") (pintype "passive"))
      (node (ref "C19") (pin "1") (pinfunction "1_1") (pintype "passive"))
      (node (ref "C20") (pin "1") (pinfunction "1_1") (pintype "passive"))
      (node (ref "C21") (pin "1") (pinfunction "1_1") (pintype "passive"))
      (node (ref "C40") (pin "+") (pinfunction "+_+") (pintype "passive"))
      (node (ref "R50") (pin "2") (pinfunction "2_2") (pintype "passive"))
      (node (ref "REG2.5") (pin "4") (pinfunction "VOUT1_4") (pintype "bidirectional"))
      (node (ref "SV5") (pin "2") (pinfunction "2_2") (pintype "passive"))
      (node (ref "U1") (pin "P120") (pinfunction "VCCAUX2_P120") (pintype "passive"))
      (node (ref "U1") (pin "P134") (pinfunction "VCCAUX3_P134") (pintype "passive"))
      (node (ref "U1") (pin "P48") (pinfunction "VCCAUX0_P48") (pintype "passive"))
      (node (ref "U1") (pin "P62") (pinfunction "VCCAUX1_P62") (pintype "passive"))
    )
    (net (code "86") (name "/VCCINT") (class "Default")
      (node (ref "C22") (pin "1") (pinfunction "1_1") (pintype "passive"))
      (node (ref "C23") (pin "1") (pinfunction "1_1") (pintype "passive"))
      (node (ref "C24") (pin "1") (pinfunction "1_1") (pintype "passive"))
      (node (ref "C25") (pin "1") (pinfunction "1_1") (pintype "passive"))
      (node (ref "C42") (pin "+") (pinfunction "+_+") (pintype "passive"))
      (node (ref "REG1.2") (pin "4") (pinfunction "VOUT1_4") (pintype "bidirectional"))
      (node (ref "SV5") (pin "1") (pinfunction "1_1") (pintype "passive"))
      (node (ref "U1") (pin "P121") (pinfunction "VCCINT2_P121") (pintype "passive"))
      (node (ref "U1") (pin "P133") (pinfunction "VCCINT3_P133") (pintype "passive"))
      (node (ref "U1") (pin "P49") (pinfunction "VCCINT0_P49") (pintype "passive"))
      (node (ref "U1") (pin "P61") (pinfunction "VCCINT1_P61") (pintype "passive"))
    )
    (net (code "87") (name "/X3") (class "Default")
      (node (ref "SV2") (pin "5") (pinfunction "5_5") (pintype "passive"))
      (node (ref "U1") (pin "P76") (pinfunction "IO_P76") (pintype "bidirectional"))
    )
    (net (code "88") (name "/X4") (class "Default")
      (node (ref "SV2") (pin "3") (pinfunction "3_3") (pintype "passive"))
      (node (ref "U1") (pin "P77") (pinfunction "IO_L20P_3_P77") (pintype "bidirectional"))
    )
    (net (code "89") (name "/X8") (class "Default")
      (node (ref "SV2") (pin "1") (pinfunction "1_1") (pintype "passive"))
      (node (ref "U1") (pin "P74") (pinfunction "IO_L01N_3VRP_3_P74") (pintype "bidirectional"))
    )
    (net (code "91") (name "GND") (class "Default")
      (node (ref "C1") (pin "1") (pinfunction "1_1") (pintype "passive"))
      (node (ref "C10") (pin "2") (pinfunction "2_2") (pintype "passive"))
      (node (ref "C11") (pin "2") (pinfunction "2_2") (pintype "passive"))
      (node (ref "C12") (pin "2") (pinfunction "2_2") (pintype "passive"))
      (node (ref "C13") (pin "2") (pinfunction "2_2") (pintype "passive"))
      (node (ref "C14") (pin "2") (pinfunction "2_2") (pintype "passive"))
      (node (ref "C15") (pin "2") (pinfunction "2_2") (pintype "passive"))
      (node (ref "C16") (pin "2") (pinfunction "2_2") (pintype "passive"))
      (node (ref "C17") (pin "2") (pinfunction "2_2") (pintype "passive"))
      (node (ref "C18") (pin "2") (pinfunction "2_2") (pintype "passive"))
      (node (ref "C19") (pin "2") (pinfunction "2_2") (pintype "passive"))
      (node (ref "C20") (pin "2") (pinfunction "2_2") (pintype "passive"))
      (node (ref "C21") (pin "2") (pinfunction "2_2") (pintype "passive"))
      (node (ref "C22") (pin "2") (pinfunction "2_2") (pintype "passive"))
      (node (ref "C23") (pin "2") (pinfunction "2_2") (pintype "passive"))
      (node (ref "C24") (pin "2") (pinfunction "2_2") (pintype "passive"))
      (node (ref "C25") (pin "2") (pinfunction "2_2") (pintype "passive"))
      (node (ref "C26") (pin "2") (pinfunction "2_2") (pintype "passive"))
      (node (ref "C27") (pin "2") (pinfunction "2_2") (pintype "passive"))
      (node (ref "C28") (pin "2") (pinfunction "2_2") (pintype "passive"))
      (node (ref "C29") (pin "2") (pinfunction "2_2") (pintype "passive"))
      (node (ref "C30") (pin "2") (pinfunction "2_2") (pintype "passive"))
      (node (ref "C31") (pin "2") (pinfunction "2_2") (pintype "passive"))
      (node (ref "C32") (pin "2") (pinfunction "2_2") (pintype "passive"))
      (node (ref "C33") (pin "-") (pinfunction "-_-") (pintype "passive"))
      (node (ref "C34") (pin "2") (pinfunction "2_2") (pintype "passive"))
      (node (ref "C37") (pin "1") (pinfunction "1_1") (pintype "passive"))
      (node (ref "C38") (pin "1") (pinfunction "1_1") (pintype "passive"))
      (node (ref "C39") (pin "-") (pinfunction "-_-") (pintype "passive"))
      (node (ref "C40") (pin "-") (pinfunction "-_-") (pintype "passive"))
      (node (ref "C41") (pin "2") (pinfunction "2_2") (pintype "passive"))
      (node (ref "C42") (pin "-") (pinfunction "-_-") (pintype "passive"))
      (node (ref "C5") (pin "1") (pinfunction "1_1") (pintype "passive"))
      (node (ref "C6") (pin "2") (pinfunction "2_2") (pintype "passive"))
      (node (ref "C7") (pin "2") (pinfunction "2_2") (pintype "passive"))
      (node (ref "C8") (pin "2") (pinfunction "2_2") (pintype "passive"))
      (node (ref "C9") (pin "2") (pinfunction "2_2") (pintype "passive"))
      (node (ref "IC1") (pin "11") (pinfunction "GND_11") (pintype "bidirectional"))
      (node (ref "IC2") (pin "4") (pinfunction "GND_4") (pintype "power_in"))
      (node (ref "IC3") (pin "3") (pinfunction "GND_3") (pintype "bidirectional"))
      (node (ref "PWR_HDR") (pin "1") (pinfunction "1_1") (pintype "passive"))
      (node (ref "R17") (pin "1") (pinfunction "1_1") (pintype "passive"))
      (node (ref "R19") (pin "1") (pinfunction "1_1") (pintype "passive"))
      (node (ref "R21") (pin "1") (pinfunction "1_1") (pintype "passive"))
      (node (ref "REG1.2") (pin "1") (pinfunction "GND_1") (pintype "bidirectional"))
      (node (ref "REG2.5") (pin "1") (pinfunction "GND_1") (pintype "bidirectional"))
      (node (ref "SV2") (pin "2") (pinfunction "2_2") (pintype "passive"))
      (node (ref "SV3") (pin "2") (pinfunction "2_2") (pintype "passive"))
      (node (ref "SV4") (pin "3") (pinfunction "3_3") (pintype "passive"))
      (node (ref "SV4") (pin "4") (pinfunction "4_4") (pintype "passive"))
      (node (ref "SV5") (pin "7") (pinfunction "7_7") (pintype "passive"))
      (node (ref "U$1") (pin "GND") (pinfunction "GND_GND") (pintype "bidirectional"))
      (node (ref "U$2") (pin "GND") (pinfunction "GND_GND") (pintype "power_in"))
      (node (ref "U$3") (pin "3") (pinfunction "VSS1_3") (pintype "power_in"))
      (node (ref "U$3") (pin "6") (pinfunction "VSS2_6") (pintype "power_in"))
      (node (ref "U$3") (pin "MT1") (pinfunction "COMMON_SW_MT1") (pintype "passive"))
      (node (ref "U$3") (pin "MT3") (pinfunction "GND_MT3") (pintype "power_in"))
      (node (ref "U$4") (pin "1") (pinfunction "GND_1") (pintype "bidirectional"))
      (node (ref "U$6") (pin "P24") (pinfunction "VSS_P24") (pintype "bidirectional"))
      (node (ref "U$6") (pin "P30") (pinfunction "CE_P30") (pintype "bidirectional"))
      (node (ref "U$7") (pin "GND") (pinfunction "GND_GND") (pintype "bidirectional"))
      (node (ref "U$8") (pin "GND") (pinfunction "GND_GND") (pintype "bidirectional"))
      (node (ref "U$9") (pin "GND") (pinfunction "GND_GND") (pintype "bidirectional"))
      (node (ref "U1") (pin "P101") (pinfunction "GND11_P101") (pintype "passive"))
      (node (ref "U1") (pin "P114") (pinfunction "GND12_P114") (pintype "passive"))
      (node (ref "U1") (pin "P117") (pinfunction "GND13_P117") (pintype "passive"))
      (node (ref "U1") (pin "P136") (pinfunction "GND14_P136") (pintype "passive"))
      (node (ref "U1") (pin "P139") (pinfunction "GND15_P139") (pintype "passive"))
      (node (ref "U1") (pin "P16") (pinfunction "GND1_P16") (pintype "passive"))
      (node (ref "U1") (pin "P22") (pinfunction "GND2_P22") (pintype "passive"))
      (node (ref "U1") (pin "P29") (pinfunction "GND3_P29") (pintype "passive"))
      (node (ref "U1") (pin "P37") (pinfunction "M1_P37") (pintype "bidirectional"))
      (node (ref "U1") (pin "P38") (pinfunction "M0_P38") (pintype "bidirectional"))
      (node (ref "U1") (pin "P39") (pinfunction "M2_P39") (pintype "bidirectional"))
      (node (ref "U1") (pin "P42") (pinfunction "GND4_P42") (pintype "passive"))
      (node (ref "U1") (pin "P45") (pinfunction "GND5_P45") (pintype "passive"))
      (node (ref "U1") (pin "P64") (pinfunction "GND6_P64") (pintype "passive"))
      (node (ref "U1") (pin "P67") (pinfunction "GND7_P67") (pintype "passive"))
      (node (ref "U1") (pin "P81") (pinfunction "GND8_P81") (pintype "passive"))
      (node (ref "U1") (pin "P88") (pinfunction "GND9_P88") (pintype "passive"))
      (node (ref "U1") (pin "P9") (pinfunction "GND0_P9") (pintype "passive"))
      (node (ref "U1") (pin "P94") (pinfunction "GND10_P94") (pintype "passive"))
      (node (ref "X1") (pin "13") (pinfunction "13_13") (pintype "passive"))
      (node (ref "X1") (pin "14") (pinfunction "14_14") (pintype "passive"))
      (node (ref "X1") (pin "17") (pinfunction "17_17") (pintype "passive"))
      (node (ref "X1") (pin "18") (pinfunction "18_18") (pintype "passive"))
      (node (ref "X1") (pin "21") (pinfunction "21_21") (pintype "passive"))
      (node (ref "X1") (pin "4") (pinfunction "4_4") (pintype "passive"))
      (node (ref "X1") (pin "5") (pinfunction "5_5") (pintype "passive"))
      (node (ref "X1") (pin "9") (pinfunction "9_9") (pintype "passive"))
      (node (ref "X3") (pin "3") (pinfunction "3_3") (pintype "passive"))
      (node (ref "X3") (pin "SH1") (pinfunction "PE1_SH1") (pintype "power_in"))
      (node (ref "X3") (pin "SH2") (pinfunction "PE2_SH2") (pintype "power_in"))
      (node (ref "X3") (pin "SH3") (pinfunction "PE3_SH3") (pintype "power_in"))
      (node (ref "X4") (pin "8") (pinfunction "F_8") (pintype "passive"))
      (node (ref "X4") (pin "G1") (pinfunction "G1_G1") (pintype "passive"))
      (node (ref "X5") (pin "8") (pinfunction "F_8") (pintype "passive"))
      (node (ref "X5") (pin "G1") (pinfunction "G1_G1") (pintype "passive"))
      (node (ref "X7") (pin "3") (pinfunction "3_3") (pintype "power_in"))
      (node (ref "X8") (pin "1") (pinfunction "1_1") (pintype "passive"))
    )
    (net (code "92") (name "Net-(C1-Pad2)") (class "Default")
      (node (ref "C1") (pin "2") (pinfunction "2_2") (pintype "passive"))
      (node (ref "R23") (pin "2") (pinfunction "2_2") (pintype "passive"))
      (node (ref "R48") (pin "1") (pinfunction "1_1") (pintype "passive"))
    )
    (net (code "93") (name "Net-(C2-Pad1)") (class "Default")
      (node (ref "C2") (pin "1") (pinfunction "1_1") (pintype "passive"))
      (node (ref "R17") (pin "2") (pinfunction "2_2") (pintype "passive"))
      (node (ref "X8") (pin "2") (pinfunction "2_2") (pintype "passive"))
      (node (ref "X8") (pin "3") (pinfunction "3_3") (pintype "passive"))
      (node (ref "X8") (pin "4") (pinfunction "4_4") (pintype "passive"))
      (node (ref "X8") (pin "5") (pinfunction "5_5") (pintype "passive"))
    )
    (net (code "94") (name "Net-(C3-Pad1)") (class "Default")
      (node (ref "C3") (pin "1") (pinfunction "1_1") (pintype "passive"))
      (node (ref "R48") (pin "2") (pinfunction "2_2") (pintype "passive"))
    )
    (net (code "95") (name "Net-(C4-Pad1)") (class "Default")
      (node (ref "C4") (pin "1") (pinfunction "1_1") (pintype "passive"))
      (node (ref "R49") (pin "2") (pinfunction "2_2") (pintype "passive"))
    )
    (net (code "96") (name "Net-(C5-Pad2)") (class "Default")
      (node (ref "C5") (pin "2") (pinfunction "2_2") (pintype "passive"))
      (node (ref "R34") (pin "2") (pinfunction "2_2") (pintype "passive"))
      (node (ref "R49") (pin "1") (pinfunction "1_1") (pintype "passive"))
    )
    (net (code "97") (name "Net-(C38-Pad2)") (class "Default")
      (node (ref "C38") (pin "2") (pinfunction "2_2") (pintype "passive"))
      (node (ref "JP2") (pin "1") (pinfunction "1_1") (pintype "passive"))
      (node (ref "Q1") (pin "2") (pinfunction "2_2") (pintype "passive"))
    )
    (net (code "98") (name "Net-(IC1-CLK)") (class "Default")
      (node (ref "IC1") (pin "3") (pinfunction "CLK_3") (pintype "bidirectional"))
      (node (ref "U1") (pin "P72") (pinfunction "CCLK_P72") (pintype "bidirectional"))
    )
    (net (code "99") (name "Net-(IC1-TDI)") (class "Default")
      (node (ref "IC1") (pin "4") (pinfunction "TDI_4") (pintype "bidirectional"))
      (node (ref "U1") (pin "P109") (pinfunction "TDO_P109") (pintype "bidirectional"))
    )
    (net (code "100") (name "Net-(IC1-{slash}CE)") (class "Default")
      (node (ref "IC1") (pin "10") (pinfunction "/CE_10") (pintype "bidirectional"))
      (node (ref "U1") (pin "P71") (pinfunction "DONE_P71") (pintype "bidirectional"))
    )
    (net (code "101") (name "Net-(IC1-{slash}CF)") (class "Default")
      (node (ref "IC1") (pin "7") (pinfunction "/CF_7") (pintype "bidirectional"))
      (node (ref "U1") (pin "P143") (pinfunction "PROG_B_P143") (pintype "bidirectional"))
    )
    (net (code "102") (name "Net-(IC3-D+)") (class "Default")
      (node (ref "IC3") (pin "29") (pinfunction "D+_29") (pintype "bidirectional"))
      (node (ref "R54") (pin "2") (pinfunction "2_2") (pintype "passive"))
    )
    (net (code "103") (name "Net-(IC3-D-)") (class "Default")
      (node (ref "IC3") (pin "30") (pinfunction "D-_30") (pintype "bidirectional"))
      (node (ref "R53") (pin "2") (pinfunction "2_2") (pintype "passive"))
    )
    (net (code "104") (name "Net-(IC3-UCAP)") (class "Default")
      (node (ref "C41") (pin "1") (pinfunction "1_1") (pintype "passive"))
      (node (ref "IC3") (pin "27") (pinfunction "UCAP_27") (pintype "bidirectional"))
    )
    (net (code "105") (name "Net-(IC3-UGND)") (class "Default")
      (node (ref "IC3") (pin "28") (pinfunction "UGND_28") (pintype "bidirectional"))
      (node (ref "X6") (pin "4") (pinfunction "4_4") (pintype "passive"))
    )
    (net (code "106") (name "Net-(IC3-XTAL1)") (class "Default")
      (node (ref "IC3") (pin "1") (pinfunction "XTAL1_1") (pintype "bidirectional"))
      (node (ref "JP2") (pin "2") (pinfunction "2_2") (pintype "passive"))
    )
    (net (code "107") (name "Net-(IC3-XTAL2{slash}PC0)") (class "Default")
      (node (ref "C37") (pin "2") (pinfunction "2_2") (pintype "passive"))
      (node (ref "IC3") (pin "2") (pinfunction "XTAL2/PC0_2") (pintype "bidirectional"))
      (node (ref "Q1") (pin "1") (pinfunction "1_1") (pintype "passive"))
    )
    (net (code "108") (name "Net-(Q5-B)") (class "Default")
      (node (ref "Q5") (pin "1") (pinfunction "B_1") (pintype "passive"))
      (node (ref "R8") (pin "2") (pinfunction "2_2") (pintype "passive"))
    )
    (net (code "109") (name "Net-(Q5-E)") (class "Default")
      (node (ref "Q5") (pin "2") (pinfunction "E_2") (pintype "passive"))
      (node (ref "R13") (pin "2") (pinfunction "2_2") (pintype "passive"))
      (node (ref "R14") (pin "2") (pinfunction "2_2") (pintype "passive"))
    )
    (net (code "110") (name "Net-(Q6-B)") (class "Default")
      (node (ref "Q6") (pin "1") (pinfunction "B_1") (pintype "passive"))
      (node (ref "R10") (pin "2") (pinfunction "2_2") (pintype "passive"))
      (node (ref "R9") (pin "2") (pinfunction "2_2") (pintype "passive"))
    )
    (net (code "111") (name "Net-(Q6-E)") (class "Default")
      (node (ref "Q6") (pin "2") (pinfunction "E_2") (pintype "passive"))
      (node (ref "R15") (pin "2") (pinfunction "2_2") (pintype "passive"))
      (node (ref "R16") (pin "2") (pinfunction "2_2") (pintype "passive"))
      (node (ref "R20") (pin "2") (pinfunction "2_2") (pintype "passive"))
    )
    (net (code "112") (name "Net-(Q7-B)") (class "Default")
      (node (ref "Q7") (pin "1") (pinfunction "B_1") (pintype "passive"))
      (node (ref "R29") (pin "2") (pinfunction "2_2") (pintype "passive"))
      (node (ref "R30") (pin "2") (pinfunction "2_2") (pintype "passive"))
    )
    (net (code "113") (name "Net-(Q7-E)") (class "Default")
      (node (ref "Q7") (pin "2") (pinfunction "E_2") (pintype "passive"))
      (node (ref "R31") (pin "2") (pinfunction "2_2") (pintype "passive"))
      (node (ref "R32") (pin "2") (pinfunction "2_2") (pintype "passive"))
      (node (ref "R33") (pin "2") (pinfunction "2_2") (pintype "passive"))
    )
    (net (code "114") (name "Net-(Q8-B)") (class "Default")
      (node (ref "Q8") (pin "1") (pinfunction "B_1") (pintype "passive"))
      (node (ref "R24") (pin "2") (pinfunction "2_2") (pintype "passive"))
      (node (ref "R25") (pin "2") (pinfunction "2_2") (pintype "passive"))
    )
    (net (code "115") (name "Net-(Q8-E)") (class "Default")
      (node (ref "Q8") (pin "2") (pinfunction "E_2") (pintype "passive"))
      (node (ref "R26") (pin "2") (pinfunction "2_2") (pintype "passive"))
      (node (ref "R27") (pin "2") (pinfunction "2_2") (pintype "passive"))
      (node (ref "R28") (pin "2") (pinfunction "2_2") (pintype "passive"))
    )
    (net (code "116") (name "Net-(R18-Pad2)") (class "Default")
      (node (ref "R18") (pin "2") (pinfunction "2_2") (pintype "passive"))
      (node (ref "R22") (pin "2") (pinfunction "2_2") (pintype "passive"))
    )
    (net (code "117") (name "Net-(R53-Pad1)") (class "Default")
      (node (ref "R53") (pin "1") (pinfunction "1_1") (pintype "passive"))
      (node (ref "X6") (pin "2") (pinfunction "2_2") (pintype "passive"))
    )
    (net (code "118") (name "Net-(R54-Pad1)") (class "Default")
      (node (ref "R54") (pin "1") (pinfunction "1_1") (pintype "passive"))
      (node (ref "X6") (pin "3") (pinfunction "3_3") (pintype "passive"))
    )
    (net (code "119") (name "Net-(T2-B)") (class "Default")
      (node (ref "C2") (pin "2") (pinfunction "2_2") (pintype "passive"))
      (node (ref "R18") (pin "1") (pinfunction "1_1") (pintype "passive"))
      (node (ref "R19") (pin "2") (pinfunction "2_2") (pintype "passive"))
      (node (ref "T2") (pin "1") (pinfunction "B_1") (pintype "passive"))
    )
    (net (code "120") (name "Net-(U$6-A0)") (class "Default")
      (node (ref "U$6") (pin "P20") (pinfunction "A0_P20") (pintype "bidirectional"))
      (node (ref "U1") (pin "P24") (pinfunction "IO_L24N_6VREF_6_P24") (pintype "bidirectional"))
    )
    (net (code "121") (name "Net-(U$6-A1)") (class "Default")
      (node (ref "U$6") (pin "P19") (pinfunction "A1_P19") (pintype "bidirectional"))
      (node (ref "U1") (pin "P23") (pinfunction "IO_L24P_6_P23") (pintype "bidirectional"))
    )
    (net (code "122") (name "Net-(U$6-A2)") (class "Default")
      (node (ref "U$6") (pin "P18") (pinfunction "A2_P18") (pintype "bidirectional"))
      (node (ref "U1") (pin "P21") (pinfunction "IO_L40N_6_P21") (pintype "bidirectional"))
    )
    (net (code "123") (name "Net-(U$6-A3)") (class "Default")
      (node (ref "U$6") (pin "P17") (pinfunction "A3_P17") (pintype "bidirectional"))
      (node (ref "U1") (pin "P20") (pinfunction "IO_L40P_6VREF_6_P20") (pintype "bidirectional"))
    )
    (net (code "124") (name "Net-(U$6-A4)") (class "Default")
      (node (ref "U$6") (pin "P16") (pinfunction "A4_P16") (pintype "bidirectional"))
      (node (ref "U1") (pin "P18") (pinfunction "IO_L40N_7VREF_7_P18") (pintype "bidirectional"))
    )
    (net (code "125") (name "Net-(U$6-A5)") (class "Default")
      (node (ref "U$6") (pin "P15") (pinfunction "A5_P15") (pintype "bidirectional"))
      (node (ref "U1") (pin "P17") (pinfunction "IO_L40P_7_P17") (pintype "bidirectional"))
    )
    (net (code "126") (name "Net-(U$6-A6)") (class "Default")
      (node (ref "U$6") (pin "P14") (pinfunction "A6_P14") (pintype "bidirectional"))
      (node (ref "U1") (pin "P15") (pinfunction "IO_L24N_7_P15") (pintype "bidirectional"))
    )
    (net (code "127") (name "Net-(U$6-A7)") (class "Default")
      (node (ref "U$6") (pin "P13") (pinfunction "A7_P13") (pintype "bidirectional"))
      (node (ref "U1") (pin "P14") (pinfunction "IO_L24P_7_P14") (pintype "bidirectional"))
    )
    (net (code "128") (name "Net-(U$6-A8)") (class "Default")
      (node (ref "U$6") (pin "P3") (pinfunction "A8_P3") (pintype "bidirectional"))
      (node (ref "U1") (pin "P4") (pinfunction "IOVREF_7_P4") (pintype "bidirectional"))
    )
    (net (code "129") (name "Net-(U$6-A9)") (class "Default")
      (node (ref "U$6") (pin "P2") (pinfunction "A9_P2") (pintype "bidirectional"))
      (node (ref "U1") (pin "P2") (pinfunction "IO_L01N_7VRP_7_P2") (pintype "bidirectional"))
    )
    (net (code "130") (name "Net-(U$6-A10)") (class "Default")
      (node (ref "U$6") (pin "P31") (pinfunction "A10_P31") (pintype "bidirectional"))
      (node (ref "U1") (pin "P35") (pinfunction "IO_L01P_6VRN_6_P35") (pintype "bidirectional"))
    )
    (net (code "131") (name "Net-(U$6-A11)") (class "Default")
      (node (ref "U$6") (pin "P1") (pinfunction "A11_P1") (pintype "bidirectional"))
      (node (ref "U1") (pin "P1") (pinfunction "IO_L01P_7VRN_7_P1") (pintype "bidirectional"))
    )
    (net (code "132") (name "Net-(U$6-A12)") (class "Default")
      (node (ref "U$6") (pin "P12") (pinfunction "A12_P12") (pintype "bidirectional"))
      (node (ref "U1") (pin "P13") (pinfunction "IO_L23N_7_P13") (pintype "bidirectional"))
    )
    (net (code "133") (name "Net-(U$6-A13)") (class "Default")
      (node (ref "U$6") (pin "P4") (pinfunction "A13_P4") (pintype "bidirectional"))
      (node (ref "U1") (pin "P5") (pinfunction "IO_L20P_7_P5") (pintype "bidirectional"))
    )
    (net (code "134") (name "Net-(U$6-A14)") (class "Default")
      (node (ref "U$6") (pin "P11") (pinfunction "A14_P11") (pintype "bidirectional"))
      (node (ref "U1") (pin "P12") (pinfunction "IO_L23P_7_P12") (pintype "bidirectional"))
    )
    (net (code "135") (name "Net-(U$6-A15)") (class "Default")
      (node (ref "U$6") (pin "P7") (pinfunction "A15_P7") (pintype "bidirectional"))
      (node (ref "U1") (pin "P8") (pinfunction "IO_L21N_7_P8") (pintype "bidirectional"))
    )
    (net (code "136") (name "Net-(U$6-A16)") (class "Default")
      (node (ref "U$6") (pin "P10") (pinfunction "A16_P10") (pintype "bidirectional"))
      (node (ref "U1") (pin "P11") (pinfunction "IO_L22N_7_P11") (pintype "bidirectional"))
    )
    (net (code "137") (name "Net-(U$6-A17)") (class "Default")
      (node (ref "U$6") (pin "P6") (pinfunction "A17_P6") (pintype "bidirectional"))
      (node (ref "U1") (pin "P7") (pinfunction "IO_L21P_7_P7") (pintype "bidirectional"))
    )
    (net (code "138") (name "Net-(U$6-A18)") (class "Default")
      (node (ref "U$6") (pin "P9") (pinfunction "A18_P9") (pintype "bidirectional"))
      (node (ref "U1") (pin "P10") (pinfunction "IO_L22P_7_P10") (pintype "bidirectional"))
    )
    (net (code "139") (name "Net-(U$6-DQ0)") (class "Default")
      (node (ref "U$6") (pin "P21") (pinfunction "DQ0_P21") (pintype "bidirectional"))
      (node (ref "U1") (pin "P25") (pinfunction "IO_L23P_6_P25") (pintype "bidirectional"))
    )
    (net (code "140") (name "Net-(U$6-DQ1)") (class "Default")
      (node (ref "U$6") (pin "P22") (pinfunction "DQ1_P22") (pintype "bidirectional"))
      (node (ref "U1") (pin "P26") (pinfunction "IO_L23N_6_P26") (pintype "bidirectional"))
    )
    (net (code "141") (name "Net-(U$6-DQ2)") (class "Default")
      (node (ref "U$6") (pin "P23") (pinfunction "DQ2_P23") (pintype "bidirectional"))
      (node (ref "U1") (pin "P27") (pinfunction "IO_L22P_6_P27") (pintype "bidirectional"))
    )
    (net (code "142") (name "Net-(U$6-DQ3)") (class "Default")
      (node (ref "U$6") (pin "P25") (pinfunction "DQ3_P25") (pintype "bidirectional"))
      (node (ref "U1") (pin "P28") (pinfunction "IO_L22N_6_P28") (pintype "bidirectional"))
    )
    (net (code "143") (name "Net-(U$6-DQ4)") (class "Default")
      (node (ref "U$6") (pin "P26") (pinfunction "DQ4_P26") (pintype "bidirectional"))
      (node (ref "U1") (pin "P30") (pinfunction "IO_L21P_6_P30") (pintype "bidirectional"))
    )
    (net (code "144") (name "Net-(U$6-DQ5)") (class "Default")
      (node (ref "U$6") (pin "P27") (pinfunction "DQ5_P27") (pintype "bidirectional"))
      (node (ref "U1") (pin "P31") (pinfunction "IO_L21N_6_P31") (pintype "bidirectional"))
    )
    (net (code "145") (name "Net-(U$6-DQ6)") (class "Default")
      (node (ref "U$6") (pin "P28") (pinfunction "DQ6_P28") (pintype "bidirectional"))
      (node (ref "U1") (pin "P32") (pinfunction "IO_L20P_6_P32") (pintype "bidirectional"))
    )
    (net (code "146") (name "Net-(U$6-DQ7)") (class "Default")
      (node (ref "U$6") (pin "P29") (pinfunction "DQ7_P29") (pintype "bidirectional"))
      (node (ref "U1") (pin "P33") (pinfunction "IO_L20N_6_P33") (pintype "bidirectional"))
    )
    (net (code "147") (name "Net-(U$6-OE)") (class "Default")
      (node (ref "U$6") (pin "P32") (pinfunction "OE_P32") (pintype "bidirectional"))
      (node (ref "U1") (pin "P36") (pinfunction "IO_L01N_6VRP_6_P36") (pintype "bidirectional"))
    )
    (net (code "148") (name "Net-(U$6-WE)") (class "Default")
      (node (ref "U$6") (pin "P5") (pinfunction "WE_P5") (pintype "bidirectional"))
      (node (ref "U1") (pin "P6") (pinfunction "IO_L20N_7_P6") (pintype "bidirectional"))
    )
    (net (code "149") (name "Net-(U1A-IO_L27N_0)") (class "Default")
      (node (ref "SV3") (pin "3") (pinfunction "3_3") (pintype "passive"))
      (node (ref "U1") (pin "P137") (pinfunction "IO_L27N_0_P137") (pintype "bidirectional"))
    )
    (net (code "150") (name "Net-(U1A-IO_L27P_0)") (class "Default")
      (node (ref "SV3") (pin "4") (pinfunction "4_4") (pintype "passive"))
      (node (ref "U1") (pin "P135") (pinfunction "IO_L27P_0_P135") (pintype "bidirectional"))
    )
    (net (code "151") (name "Net-(U1A-IO_L30N_0)") (class "Default")
      (node (ref "SV3") (pin "5") (pinfunction "5_5") (pintype "passive"))
      (node (ref "U1") (pin "P132") (pinfunction "IO_L30N_0_P132") (pintype "bidirectional"))
    )
    (net (code "152") (name "Net-(U1A-IO_L31N_0)") (class "Default")
      (node (ref "SV3") (pin "6") (pinfunction "6_6") (pintype "passive"))
      (node (ref "U1") (pin "P130") (pinfunction "IO_L31N_0_P130") (pintype "bidirectional"))
    )
    (net (code "153") (name "Net-(U1A-IO_L31P_0VREF_0)") (class "Default")
      (node (ref "SV3") (pin "7") (pinfunction "7_7") (pintype "passive"))
      (node (ref "U1") (pin "P129") (pinfunction "IO_L31P_0VREF_0_P129") (pintype "bidirectional"))
    )
    (net (code "154") (name "Net-(U1A-IO_L32N_0GCLK7)") (class "Default")
      (node (ref "SV3") (pin "8") (pinfunction "8_8") (pintype "passive"))
      (node (ref "U1") (pin "P128") (pinfunction "IO_L32N_0GCLK7_P128") (pintype "bidirectional"))
    )
    (net (code "155") (name "Net-(U1A-IO_L32P_0GCLK6)") (class "Default")
      (node (ref "SV3") (pin "9") (pinfunction "9_9") (pintype "passive"))
      (node (ref "U1") (pin "P127") (pinfunction "IO_L32P_0GCLK6_P127") (pintype "bidirectional"))
    )
    (net (code "156") (name "Net-(U1C-IO_L31N_1VREF_1)") (class "Default")
      (node (ref "SV3") (pin "10") (pinfunction "10_10") (pintype "passive"))
      (node (ref "U1") (pin "P123") (pinfunction "IO_L31N_1VREF_1_P123") (pintype "bidirectional"))
    )
    (net (code "157") (name "Net-(U1N-TCK)") (class "Default")
      (node (ref "R2") (pin "1") (pinfunction "1_1") (pintype "passive"))
      (node (ref "U1") (pin "P110") (pinfunction "TCK_P110") (pintype "bidirectional"))
    )
    (net (code "158") (name "Net-(U1N-TDI)") (class "Default")
      (node (ref "R1") (pin "1") (pinfunction "1_1") (pintype "passive"))
      (node (ref "U1") (pin "P144") (pinfunction "TDI_P144") (pintype "bidirectional"))
    )
    (net (code "159") (name "Net-(U1N-TMS)") (class "Default")
      (node (ref "R3") (pin "1") (pinfunction "1_1") (pintype "passive"))
      (node (ref "U1") (pin "P111") (pinfunction "TMS_P111") (pintype "bidirectional"))
    )
    (net (code "160") (name "unconnected-(IC1-NC.1-Pad2)") (class "Default")
      (node (ref "IC1") (pin "2") (pinfunction "NC.1_2") (pintype "bidirectional"))
    )
    (net (code "161") (name "unconnected-(IC1-NC.2-Pad9)") (class "Default")
      (node (ref "IC1") (pin "9") (pinfunction "NC.2_9") (pintype "bidirectional"))
    )
    (net (code "162") (name "unconnected-(IC1-NC.3-Pad12)") (class "Default")
      (node (ref "IC1") (pin "12") (pinfunction "NC.3_12") (pintype "bidirectional"))
    )
    (net (code "163") (name "unconnected-(IC1-NC.4-Pad14)") (class "Default")
      (node (ref "IC1") (pin "14") (pinfunction "NC.4_14") (pintype "bidirectional"))
    )
    (net (code "164") (name "unconnected-(IC1-NC.5-Pad15)") (class "Default")
      (node (ref "IC1") (pin "15") (pinfunction "NC.5_15") (pintype "bidirectional"))
    )
    (net (code "165") (name "unconnected-(IC1-NC.6-Pad16)") (class "Default")
      (node (ref "IC1") (pin "16") (pinfunction "NC.6_16") (pintype "bidirectional"))
    )
    (net (code "166") (name "unconnected-(IC1-{slash}CEO-Pad13)") (class "Default")
      (node (ref "IC1") (pin "13") (pinfunction "/CEO_13") (pintype "bidirectional"))
    )
    (net (code "167") (name "unconnected-(REG1.2-VOUT2-Pad2)") (class "Default")
      (node (ref "REG1.2") (pin "2") (pinfunction "VOUT2_2") (pintype "bidirectional"))
    )
    (net (code "168") (name "unconnected-(REG2.5-VOUT2-Pad2)") (class "Default")
      (node (ref "REG2.5") (pin "2") (pinfunction "VOUT2_2") (pintype "bidirectional"))
    )
    (net (code "169") (name "unconnected-(U$2-TRI-PadENA)") (class "Default")
      (node (ref "U$2") (pin "ENA") (pinfunction "TRI_ENA") (pintype "input"))
    )
    (net (code "170") (name "unconnected-(U$3-CARD_DETECT-PadCD)") (class "Default")
      (node (ref "U$3") (pin "CD") (pinfunction "CARD_DETECT_CD") (pintype "passive"))
    )
    (net (code "171") (name "unconnected-(U$3-DAT1-Pad8)") (class "Default")
      (node (ref "U$3") (pin "8") (pinfunction "DAT1_8") (pintype "bidirectional"))
    )
    (net (code "172") (name "unconnected-(U$3-DAT2-Pad9)") (class "Default")
      (node (ref "U$3") (pin "9") (pinfunction "DAT2_9") (pintype "bidirectional"))
    )
    (net (code "173") (name "unconnected-(U$3-WRITE_PROTECT-PadWP)") (class "Default")
      (node (ref "U$3") (pin "WP") (pinfunction "WRITE_PROTECT_WP") (pintype "passive"))
    )
    (net (code "174") (name "unconnected-(U$4-VOUT2-Pad2)") (class "Default")
      (node (ref "U$4") (pin "2") (pinfunction "VOUT2_2") (pintype "bidirectional"))
    )
    (net (code "175") (name "unconnected-(U1N-HSWAP_EN-PadP142)") (class "Default")
      (node (ref "U1") (pin "P142") (pinfunction "HSWAP_EN_P142") (pintype "bidirectional"))
    )
    (net (code "176") (name "unconnected-(X1-Pad10)") (class "Default")
      (node (ref "X1") (pin "10") (pinfunction "10_10") (pintype "passive"))
    )
    (net (code "177") (name "unconnected-(X1-Pad12)") (class "Default")
      (node (ref "X1") (pin "12") (pinfunction "12_12") (pintype "passive"))
    )
    (net (code "178") (name "unconnected-(X3-Pad2)") (class "Default")
      (node (ref "X3") (pin "2") (pinfunction "2_2") (pintype "passive"))
    )
    (net (code "179") (name "unconnected-(X3-Pad8)") (class "Default")
      (node (ref "X3") (pin "8") (pinfunction "8_8") (pintype "passive"))
    )
    (net (code "180") (name "unconnected-(X4-PadG2)") (class "Default")
      (node (ref "X4") (pin "G2") (pinfunction "G2_G2") (pintype "passive"))
    )
    (net (code "181") (name "unconnected-(X5-PadG2)") (class "Default")
      (node (ref "X5") (pin "G2") (pinfunction "G2_G2") (pintype "passive"))
    )
    (net (code "182") (name "unconnected-(X6-Pad1)") (class "Default")
      (node (ref "X6") (pin "1") (pinfunction "1_1") (pintype "passive"))
    )
  )
)
